# TinyShuffle_v_0b.net
KiCad netlist of a schematic drawn in Altium Designer
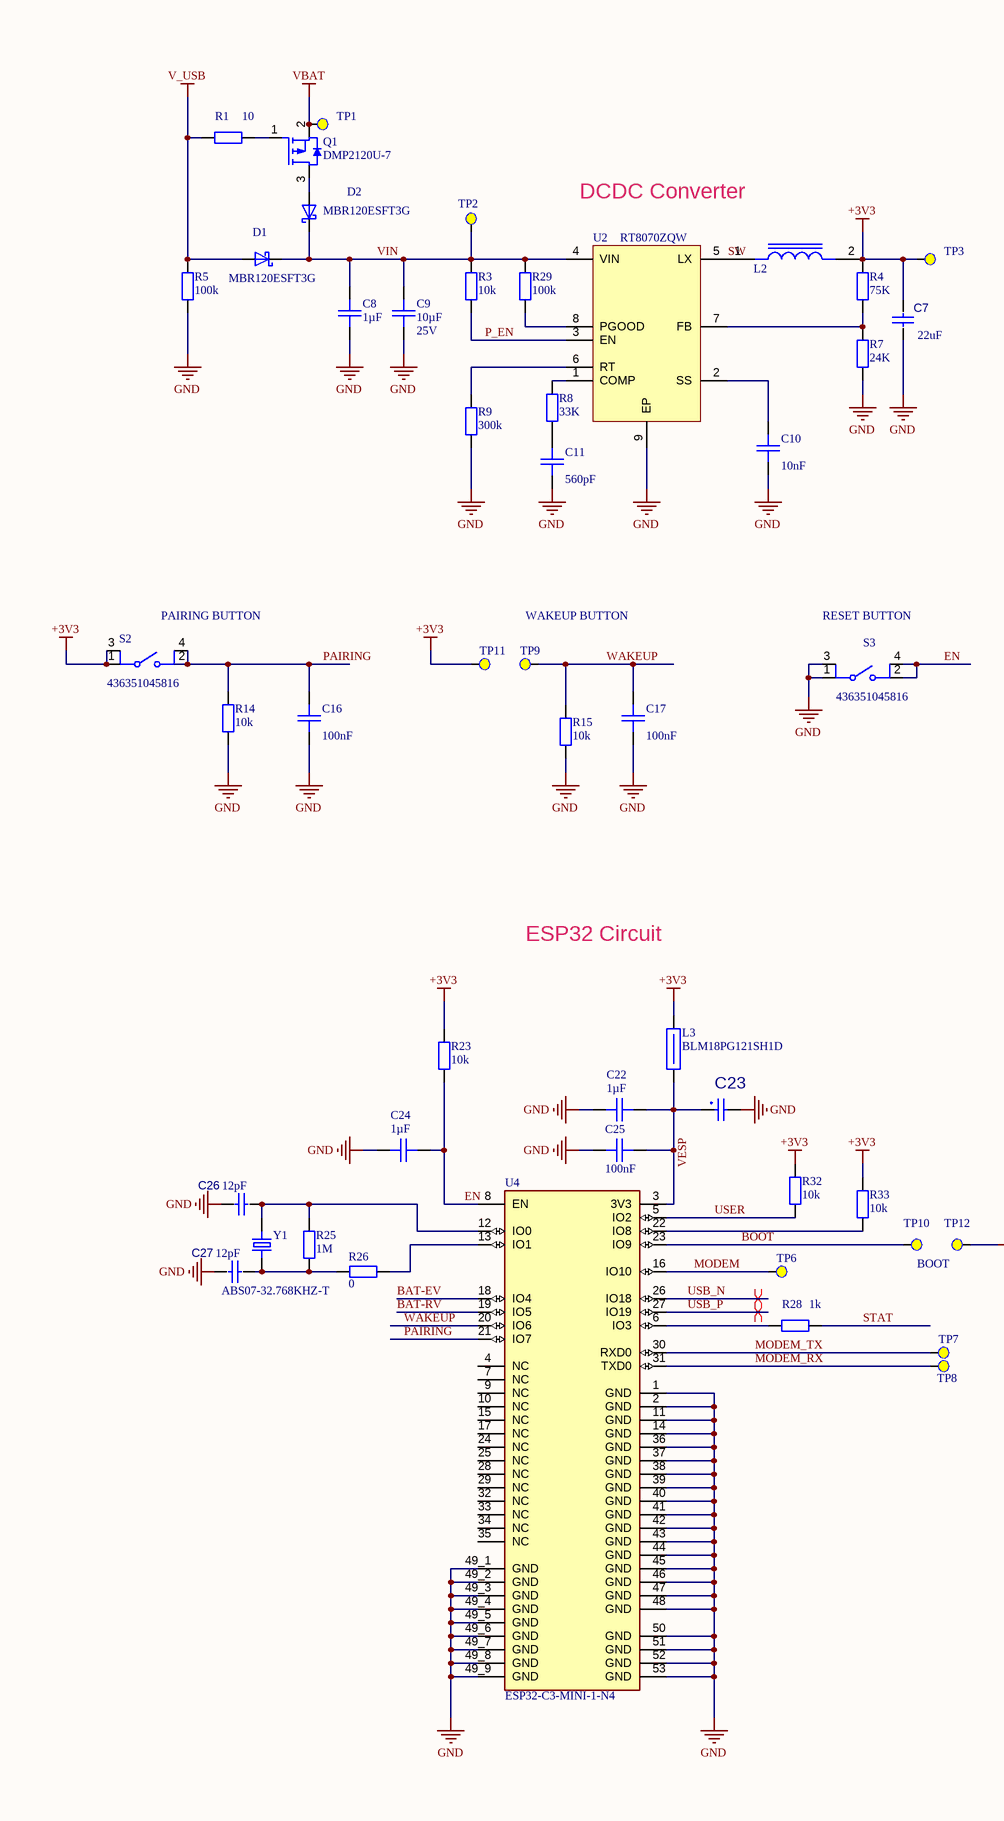
[diagram p0: TinyShuffle v.0b.SchDoc, left]
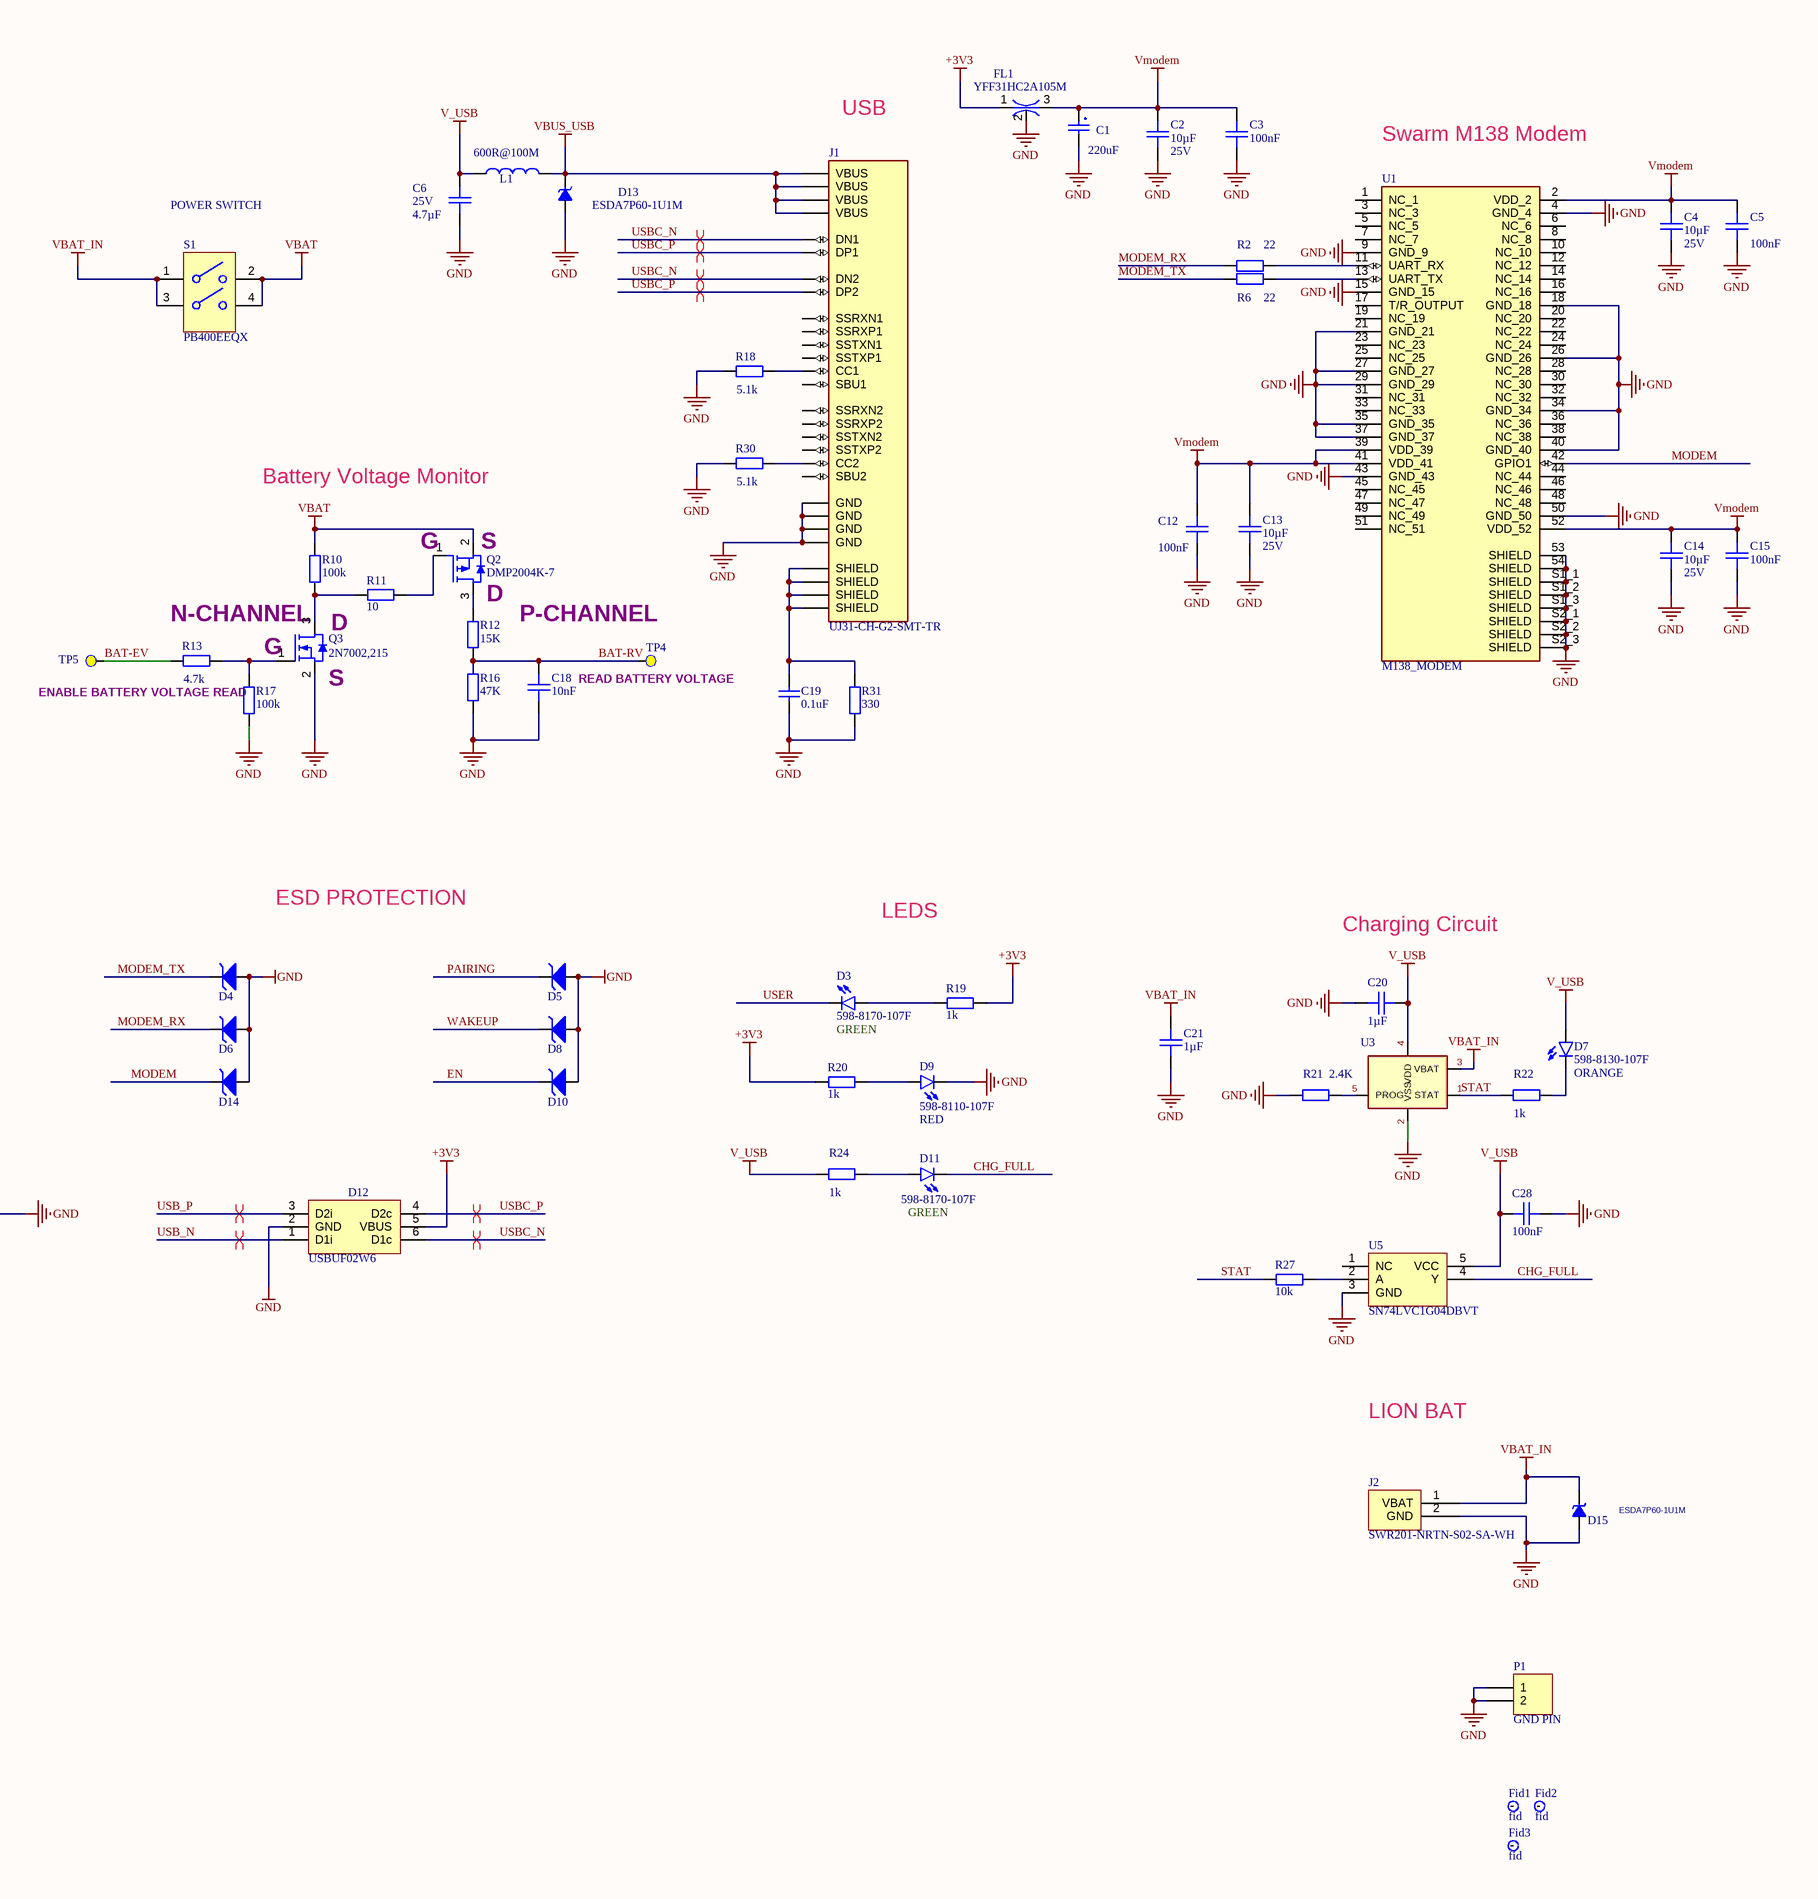
[diagram p1: TinyShuffle v.0b.SchDoc, right]

(export (version "E")
  (design (tool "Eeschema 10.0.6"))
  (components
    (comp (ref "C1")
      (value "APXA6R3ARA221MH7")
      (footprint "CHEMI-H70")
      (description "CAP ALUM POLY 220UF 20% 6.3V SMD")
      (fields
        (field (name "MANUFACTURER") "Nippon Chemi-Con")
        (field (name "MPN") "APXA6R3ARA221MH70G")
        (field (name "CAPACITANCE") "220uF")
      )
      (libsource (lib "TinyShuffle v.0b") (part "APXA6R3ARA221MH7"))
    )
    (comp (ref "C2")
      (value "GRM188R61E106MA73J")
      (footprint "CAPC160X80X90L35L")
      (description "CAP CER 10UF 25V X5R 0603")
      (fields
        (field (name "TOLERANCE") "20%")
        (field (name "MANUFACTURER") "Murata Electronics")
        (field (name "CAPACITANCE") "10µF")
        (field (name "VOLTAGE RATING") "25V")
      )
      (libsource (lib "VDroid Server") (part "CAP general symbol S00567"))
    )
    (comp (ref "C3")
      (value "CL10B104KB8NNWC")
      (footprint "CAPC160X80X90L35L")
      (description "CAP CER 0.1UF 50V X7R 0603")
      (fields
        (field (name "CAPACITANCE") "100nF")
        (field (name "TOLERANCE") "10%")
        (field (name "MANUFACTURER") "Samsung Electro-Mechanics")
      )
      (libsource (lib "VDroid Server") (part "CAP general symbol S00567"))
    )
    (comp (ref "C4")
      (value "GRM188R61E106MA73J")
      (footprint "CAPC160X80X90L35L")
      (description "CAP CER 10UF 25V X5R 0603")
      (fields
        (field (name "TOLERANCE") "20%")
        (field (name "MANUFACTURER") "Murata Electronics")
        (field (name "CAPACITANCE") "10µF")
        (field (name "VOLTAGE RATING") "25V")
      )
      (libsource (lib "VDroid Server") (part "CAP general symbol S00567"))
    )
    (comp (ref "C5")
      (value "CL10B104KB8NNWC")
      (footprint "CAPC160X80X90L35L")
      (description "CAP CER 0.1UF 50V X7R 0603")
      (fields
        (field (name "CAPACITANCE") "100nF")
        (field (name "TOLERANCE") "10%")
        (field (name "MANUFACTURER") "Samsung Electro-Mechanics")
      )
      (libsource (lib "VDroid Server") (part "CAP general symbol S00567"))
    )
    (comp (ref "C6")
      (value "GRM188R61E475KE11D")
      (footprint "CAPC160X80X90L35L")
      (description "CAP CER 4.7UF 25V X5R 0603")
      (fields
        (field (name "VOLTAGE RATING") "25V")
        (field (name "TOLERANCE") "10%")
        (field (name "CAPACITANCE") "4.7µF")
        (field (name "MANUFACTURER") "Murata Electronics")
      )
      (libsource (lib "VDroid Server") (part "CAP general symbol S00567"))
    )
    (comp (ref "C7")
      (value "22uF")
      (footprint "CAPC2012X135N")
      (description "CAP CER 22UF 16V X5R 0805")
      (fields
        (field (name "MANUFACTURER") "Samsung Electro-Mechanics")
        (field (name "MPN") "CL21A226MOQNNNE")
      )
      (libsource (lib "TinyShuffle v.0") (part "CL21A226MOQNNNE"))
    )
    (comp (ref "C8")
      (value "CL10A105KA8NNNC")
      (footprint "CAPC160X80X90L35L")
      (description "CAP CER 1UF 25V X5R 0603")
      (fields
        (field (name "MANUFACTURER") "Samsung Electro-Mechanics")
        (field (name "TOLERANCE") "10%")
        (field (name "CAPACITANCE") "1µF")
      )
      (libsource (lib "VDroid Server") (part "CAP general symbol S00567"))
    )
    (comp (ref "C9")
      (value "GRM188R61E106MA73J")
      (footprint "CAPC160X80X90L35L")
      (description "CAP CER 10UF 25V X5R 0603")
      (fields
        (field (name "TOLERANCE") "20%")
        (field (name "MANUFACTURER") "Murata Electronics")
        (field (name "CAPACITANCE") "10µF")
        (field (name "VOLTAGE RATING") "25V")
      )
      (libsource (lib "VDroid Server") (part "CAP general symbol S00567"))
    )
    (comp (ref "C10")
      (value "CL10B103KB8NNNC")
      (footprint "CAPC160X80X90L35L")
      (description "CAP CER 10000PF 50V X7R 0603")
      (fields
        (field (name "CAPACITANCE") "10nF")
        (field (name "TOLERANCE") "10%")
        (field (name "MANUFACTURER") "Samsung Electro-Mechanics")
      )
      (libsource (lib "VDroid Server") (part "CAP general symbol S00567"))
    )
    (comp (ref "C11")
      (value "CL10C561JB8NFNC")
      (footprint "CAPC160X80X90L35L")
      (description "CAP CER 560PF 50V C0G/NP0 0603")
      (fields
        (field (name "CAPACITANCE") "560pF")
        (field (name "TOLERANCE") "10%")
        (field (name "MANUFACTURER") "Samsung Electro-Mechanics")
      )
      (libsource (lib "VDroid Server") (part "CAP general symbol S00567"))
    )
    (comp (ref "C12")
      (value "CL10B104KB8NNWC")
      (footprint "CAPC160X80X90L35L")
      (description "CAP CER 0.1UF 50V X7R 0603")
      (fields
        (field (name "CAPACITANCE") "100nF")
        (field (name "TOLERANCE") "10%")
        (field (name "MANUFACTURER") "Samsung Electro-Mechanics")
      )
      (libsource (lib "VDroid Server") (part "CAP general symbol S00567"))
    )
    (comp (ref "C13")
      (value "GRM188R61E106MA73J")
      (footprint "CAPC160X80X90L35L")
      (description "CAP CER 10UF 25V X5R 0603")
      (fields
        (field (name "TOLERANCE") "20%")
        (field (name "MANUFACTURER") "Murata Electronics")
        (field (name "CAPACITANCE") "10µF")
        (field (name "VOLTAGE RATING") "25V")
      )
      (libsource (lib "VDroid Server") (part "CAP general symbol S00567"))
    )
    (comp (ref "C14")
      (value "GRM188R61E106MA73J")
      (footprint "CAPC160X80X90L35L")
      (description "CAP CER 10UF 25V X5R 0603")
      (fields
        (field (name "TOLERANCE") "20%")
        (field (name "MANUFACTURER") "Murata Electronics")
        (field (name "CAPACITANCE") "10µF")
        (field (name "VOLTAGE RATING") "25V")
      )
      (libsource (lib "VDroid Server") (part "CAP general symbol S00567"))
    )
    (comp (ref "C15")
      (value "CL10B104KB8NNWC")
      (footprint "CAPC160X80X90L35L")
      (description "CAP CER 0.1UF 50V X7R 0603")
      (fields
        (field (name "CAPACITANCE") "100nF")
        (field (name "TOLERANCE") "10%")
        (field (name "MANUFACTURER") "Samsung Electro-Mechanics")
      )
      (libsource (lib "VDroid Server") (part "CAP general symbol S00567"))
    )
    (comp (ref "C16")
      (value "CL10B104KB8NNWC")
      (footprint "CAPC160X80X90L35L")
      (description "CAP CER 0.1UF 50V X7R 0603")
      (fields
        (field (name "CAPACITANCE") "100nF")
        (field (name "TOLERANCE") "10%")
        (field (name "MANUFACTURER") "Samsung Electro-Mechanics")
      )
      (libsource (lib "VDroid Server") (part "CAP general symbol S00567"))
    )
    (comp (ref "C17")
      (value "CL10B104KB8NNWC")
      (footprint "CAPC160X80X90L35L")
      (description "CAP CER 0.1UF 50V X7R 0603")
      (fields
        (field (name "CAPACITANCE") "100nF")
        (field (name "TOLERANCE") "10%")
        (field (name "MANUFACTURER") "Samsung Electro-Mechanics")
      )
      (libsource (lib "VDroid Server") (part "CAP general symbol S00567"))
    )
    (comp (ref "C18")
      (value "GCM1885C1H103JA16D")
      (footprint "CAPC160X80X90L35L")
      (description "CAP CER 10000PF 50V NP0 0603")
      (fields
        (field (name "CAPACITANCE") "10nF")
        (field (name "TOLERANCE") "5%")
        (field (name "MANUFACTURER") "Murata Electronics")
      )
      (libsource (lib "VDroid Server") (part "CAP general symbol S00567"))
    )
    (comp (ref "C19")
      (value "0.1uF")
      (footprint "0603 CAP")
      (description "CAP CER 0.1UF 100V X7R 0603")
      (fields (field (name "MANUFACTURER") "Samsung") (field (name "MPN") "CL10B104KC8NNNC"))
      (libsource (lib "Capacitors") (part "0603-X7R-100V-0.1uF"))
    )
    (comp (ref "C20")
      (value "CL10A105KA8NNNC")
      (footprint "CAPC160X80X90L35L")
      (description "CAP CER 1UF 25V X5R 0603")
      (fields
        (field (name "MANUFACTURER") "Samsung Electro-Mechanics")
        (field (name "TOLERANCE") "10%")
        (field (name "CAPACITANCE") "1µF")
      )
      (libsource (lib "VDroid Server") (part "CAP general symbol S00567"))
    )
    (comp (ref "C21")
      (value "CL10A105KA8NNNC")
      (footprint "CAPC160X80X90L35L")
      (description "CAP CER 1UF 25V X5R 0603")
      (fields
        (field (name "MANUFACTURER") "Samsung Electro-Mechanics")
        (field (name "TOLERANCE") "10%")
        (field (name "CAPACITANCE") "1µF")
      )
      (libsource (lib "VDroid Server") (part "CAP general symbol S00567"))
    )
    (comp (ref "C22")
      (value "CL10A105KA8NNNC")
      (footprint "CAPC160X80X90L35L")
      (description "CAP CER 1UF 25V X5R 0603")
      (fields
        (field (name "MANUFACTURER") "Samsung Electro-Mechanics")
        (field (name "TOLERANCE") "10%")
        (field (name "CAPACITANCE") "1µF")
      )
      (libsource (lib "VDroid Server") (part "CAP general symbol S00567"))
    )
    (comp (ref "C23")
      (value "APXA6R3ARA221MH7")
      (footprint "CHEMI-H70")
      (description "CAP ALUM POLY 220UF 20% 6.3V SMD")
      (fields (field (name "MANUFACTURER") "Nippon Chemi-Con") (field (name "MPN") "APXA6R3ARA221MH70G"))
      (libsource (lib "TinyShuffle v.0b") (part "APXA6R3ARA221MH7"))
    )
    (comp (ref "C24")
      (value "CL10A105KA8NNNC")
      (footprint "CAPC160X80X90L35L")
      (description "CAP CER 1UF 25V X5R 0603")
      (fields
        (field (name "MANUFACTURER") "Samsung Electro-Mechanics")
        (field (name "TOLERANCE") "10%")
        (field (name "CAPACITANCE") "1µF")
      )
      (libsource (lib "VDroid Server") (part "CAP general symbol S00567"))
    )
    (comp (ref "C25")
      (value "CL10B104KB8NNWC")
      (footprint "CAPC160X80X90L35L")
      (description "CAP CER 0.1UF 50V X7R 0603")
      (fields
        (field (name "CAPACITANCE") "100nF")
        (field (name "TOLERANCE") "10%")
        (field (name "MANUFACTURER") "Samsung Electro-Mechanics")
      )
      (libsource (lib "VDroid Server") (part "CAP general symbol S00567"))
    )
    (comp (ref "C26")
      (value "12pF")
      (footprint "0603 Capacitor")
      (description "CAP CER 12PF NP0 0603")
      (fields (field (name "MANUFACTURER") "Murata Electronics") (field (name "MPN") "GRM1885C1H120JA01J"))
      (libsource (lib "*") (part "CAPC1608N-0.1UF"))
    )
    (comp (ref "C27")
      (value "12pF")
      (footprint "0603 Capacitor")
      (description "CAP CER 12PF NP0 0603")
      (fields (field (name "MANUFACTURER") "Murata Electronics") (field (name "MPN") "GRM1885C1H120JA01J"))
      (libsource (lib "*") (part "CAPC1608N-0.1UF"))
    )
    (comp (ref "C28")
      (value "CL10B104KB8NNWC")
      (footprint "CAPC160X80X90L35L")
      (description "CAP CER 0.1UF 50V X7R 0603")
      (fields
        (field (name "CAPACITANCE") "100nF")
        (field (name "TOLERANCE") "10%")
        (field (name "MANUFACTURER") "Samsung Electro-Mechanics")
      )
      (libsource (lib "VDroid Server") (part "CAP general symbol S00567"))
    )
    (comp (ref "D1")
      (value "MBR120ESFT3G")
      (footprint "SODFL3616X98N")
      (description "DIODE SCHOTTKY 20V 1A SOD123FL")
      (fields (field (name "GENERIC PART") "no") (field (name "MANUFACTURER") "ON"))
      (libsource (lib "TinyShuffle v.0b") (part "MBR0520"))
    )
    (comp (ref "D2")
      (value "MBR120ESFT3G")
      (footprint "SODFL3616X98N")
      (description "DIODE SCHOTTKY 20V 1A SOD123FL")
      (fields (field (name "GENERIC PART") "no") (field (name "MANUFACTURER") "ON"))
      (libsource (lib "TinyShuffle v.0b") (part "MBR0520"))
    )
    (comp (ref "D3")
      (value "598-8170-107F")
      (footprint "LEDC2012X70N")
      (description "Green 566nm LED Indication - Discrete 2V 0805 (2012 Metric)")
      (fields (field (name "MANUFACTURER") "Dialight") (field (name "ALTIUM_VALUE") "GREEN"))
      (libsource (lib "TinyShuffle v.0") (part "598_SERIES_LED"))
    )
    (comp (ref "D4")
      (value "CDSOD323-T03SC")
      (footprint "SOD2513X120N")
      (description "TVS DIODE 3.3VWM 10.9VC SOD323")
      (fields (field (name "MANUFACTURER") "Bourns Inc."))
      (libsource (lib "TinyShuffle v.0b") (part "CDSOD323-T03SC"))
    )
    (comp (ref "D5")
      (value "CDSOD323-T03SC")
      (footprint "SOD2513X120N")
      (description "TVS DIODE 3.3VWM 10.9VC SOD323")
      (fields (field (name "MANUFACTURER") "Bourns Inc."))
      (libsource (lib "TinyShuffle v.0b") (part "CDSOD323-T03SC"))
    )
    (comp (ref "D6")
      (value "CDSOD323-T03SC")
      (footprint "SOD2513X120N")
      (description "TVS DIODE 3.3VWM 10.9VC SOD323")
      (fields (field (name "MANUFACTURER") "Bourns Inc."))
      (libsource (lib "TinyShuffle v.0b") (part "CDSOD323-T03SC"))
    )
    (comp (ref "D7")
      (value "598-8130-107F")
      (footprint "TinyShuffle v.0:LEDC2012X70N")
      (description "Orange 605nm LED Indication - Discrete 2V 0805 (2012 Metric)")
      (fields (field (name "MANUFACTURER") "Dialight") (field (name "ALTIUM_VALUE") "ORANGE"))
      (libsource (lib "TinyShuffle v.0") (part "598_SERIES_LED"))
    )
    (comp (ref "D8")
      (value "CDSOD323-T03SC")
      (footprint "SOD2513X120N")
      (description "TVS DIODE 3.3VWM 10.9VC SOD323")
      (fields (field (name "MANUFACTURER") "Bourns Inc."))
      (libsource (lib "TinyShuffle v.0b") (part "CDSOD323-T03SC"))
    )
    (comp (ref "D9")
      (value "598-8110-107F")
      (footprint "TinyShuffle v.0:LEDC2012X70N")
      (description "Red 635nm LED Indication - Discrete 2.2V 0805 _2012 Metric_")
      (fields (field (name "MANUFACTURER") "Dialight") (field (name "ALTIUM_VALUE") "RED"))
      (libsource (lib "TinyShuffle v.0") (part "598_SERIES_LED"))
    )
    (comp (ref "D10")
      (value "CDSOD323-T03SC")
      (footprint "SOD2513X120N")
      (description "TVS DIODE 3.3VWM 10.9VC SOD323")
      (fields (field (name "MANUFACTURER") "Bourns Inc."))
      (libsource (lib "TinyShuffle v.0b") (part "CDSOD323-T03SC"))
    )
    (comp (ref "D11")
      (value "598-8170-107F")
      (footprint "TinyShuffle v.0:LEDC2012X70N")
      (description "Green 566nm LED Indication - Discrete 2V 0805 (2012 Metric)")
      (fields (field (name "MANUFACTURER") "Dialight") (field (name "ALTIUM_VALUE") "GREEN"))
      (libsource (lib "TinyShuffle v.0") (part "598_SERIES_LED"))
    )
    (comp (ref "D12")
      (value "USBUF02W6")
      (footprint "SOT323-6L")
      (description "FILTER RC(PI) 22 OHM/47PF SMD")
      (fields (field (name "MANUFACTURER") "STMicroelectronics"))
      (libsource (lib "Diodes") (part "NUF2221W1T2G"))
    )
    (comp (ref "D13")
      (value "ESDA7P60-1U1M")
      (footprint "ST_1610")
      (description "TVS DIODE 5V 11.6V 1610")
      (fields (field (name "MANUFACTURER") "STMicroelectronics"))
      (libsource (lib "Diodes") (part "ESDA7P60-1U1M"))
    )
    (comp (ref "D14")
      (value "CDSOD323-T03SC")
      (footprint "SOD2513X120N")
      (description "TVS DIODE 3.3VWM 10.9VC SOD323")
      (fields (field (name "MANUFACTURER") "Bourns Inc."))
      (libsource (lib "TinyShuffle v.0b") (part "CDSOD323-T03SC"))
    )
    (comp (ref "D15")
      (value "ESDA7P60-1U1M")
      (footprint "ST_1610")
      (description "TVS DIODE 5V 11.6V 1610")
      (fields (field (name "MANUFACTURER") "STMicroelectronics"))
      (libsource (lib "Diodes") (part "ESDA7P60-1U1M"))
    )
    (comp (ref "Fid1") (value "fid") (footprint "Fiducial mark 1") (libsource (lib "SensiEdge") (part "fid")))
    (comp (ref "Fid2") (value "fid") (footprint "Fiducial mark 1") (libsource (lib "SensiEdge") (part "fid")))
    (comp (ref "Fid3") (value "fid") (footprint "Fiducial mark 1") (libsource (lib "SensiEdge") (part "fid")))
    (comp (ref "FL1")
      (value "YFF31HC2A105M")
      (footprint "FIL_YFF31HC2A105M")
      (description "1ÂµF Feed Through Capacitor 100V 6A 5mOhm 1206 (3216 Metric), 4 PC Pad")
      (fields (field (name "MANUFACTURER") "TDK") (field (name "DIGI-KEY_PART_NUMBER") "445-16151-1-ND"))
      (libsource (lib "TinyShuffle v.0") (part "YFF31HC2A105M"))
    )
    (comp (ref "J1")
      (value "UJ31-CH-G2-SMT-TR")
      (footprint "CUI_UJ31-CH-G2-SMT-TR")
      (description "Type C, USB 3.1 Gen 2, 5 A, Right Angle, Surface Mount _SMT_, USB Receptacle")
      (fields (field (name "MANUFACTURER") "CUI Devices"))
      (libsource (lib "TinyShuffle v.0b") (part "UJ31-CH-G2-SMT-TR"))
    )
    (comp (ref "J2")
      (value "SWR201-NRTN-S02-SA-WH")
      (footprint "JST_B2B-PH-K-S(LF)(SN)")
      (description "Connector Header, PH Series, 2 Position, 2.00mm, Through Hole, Press-Fit, Solder, Natural")
      (fields (field (name "MANUFACTURER") "Sullins Connector Solutions"))
      (libsource (lib "Schlib1") (part "Battery Connector"))
    )
    (comp (ref "L1")
      (value "600R@100M")
      (footprint "0805 Ferrite Bead 2012")
      (description "FERRITE BEAD 600 OHM 0805 2A")
      (fields (field (name "MANUFACTURER") "Vishay Dale") (field (name "MPN") "ILHB0805ER601V"))
      (libsource (lib "Inductors") (part "ILHB0805ER601V"))
    )
    (comp (ref "L2")
      (value "SRP4020FA-2R0M")
      (footprint "IND_SRP4020FA-1R0M")
      (description "2 µH Shielded Drum Core, Wirewound Inductor 8.2 A 23.3mOhm Max Nonstandard -")
      (fields (field (name "MANUFACTURER") "Bourns Inc.") (field (name "TOLERANCE") "20%"))
      (libsource (lib "TinyShuffle v.0b") (part "SRP4020FA-2R0M"))
    )
    (comp (ref "L3")
      (value "BLM18PG121SH1D")
      (footprint "0603 Ferrite Bead 1608")
      (description "FERRITE BEAD 120 OHM 0603 1LN")
      (fields (field (name "MANUFACTURER") "Murata Electronics North America"))
      (libsource (lib "Acorai-WearablePatch") (part "ferrite bead"))
    )
    (comp (ref "P1")
      (value "GND PIN")
      (footprint "HDR1X2")
      (description "Header, 2-Pin")
      (fields (field (name "PUBLISHER") "Altium Limited"))
      (libsource (lib "Miscellaneous Connectors") (part "Header 2"))
    )
    (comp (ref "Q1")
      (value "DMP2120U-7")
      (footprint "SOT23-3P95_237X112L50X40L")
      (description "MOSFET P-CH 20V 3.8A SOT23")
      (fields (field (name "MANUFACTURER") "Diodes Incorporated"))
      (libsource (lib "VDroid Server") (part "P-type channel MOSFET S00673 (1-G 2-S 3-D)"))
    )
    (comp (ref "Q2")
      (value "DMP2004K-7")
      (footprint "SOT23-3P95_237X112L50X40L")
      (description "MOSFET P-CH 20V 600MA SOT23-3")
      (fields (field (name "MANUFACTURER") "Diodes Incorporated"))
      (libsource (lib "VDroid Server") (part "P-type channel MOSFET S00673 (1-G 2-S 3-D)"))
    )
    (comp (ref "Q3")
      (value "2N7002,215")
      (footprint "SOT23-3P95_237X112L50X40L")
      (description "Power MOSFET, N Channel, 60 V, 300 mA, 2.8 ohm, SOT-23, Surface Mount")
      (fields (field (name "MANUFACTURER") "Nexperia USA Inc."))
      (libsource (lib "VDroid Server") (part "N-type channel MOSFET S00674 (1-G 2-S 3-D)"))
    )
    (comp (ref "R1")
      (value "RC0603FR-0710RL")
      (footprint "RESC160X80X45L30L")
      (description "RES 10 OHM 1% 1/10W 0603")
      (fields (field (name "RESISTANCE") "10") (field (name "POWER") "100mW") (field (name "TOLERANCE") "1%"))
      (libsource (lib "VDroid Server") (part "RES general symbol S00555"))
    )
    (comp (ref "R2")
      (value "RC0603FR-0722RL")
      (footprint "RESC160X80X45L30L")
      (description "RES 22 OHM 1% 1/10W 0603")
      (fields (field (name "RESISTANCE") "22") (field (name "POWER") "100mW") (field (name "TOLERANCE") "1%"))
      (libsource (lib "VDroid Server") (part "RES general symbol S00555"))
    )
    (comp (ref "R3")
      (value "RT0603DRD0710KL")
      (footprint "RESC160X80X45L30L")
      (description "RES SMD 10K OHM 0.5% 1/10W 0603")
      (fields
        (field (name "MANUFACTURER") "YAGEO")
        (field (name "POWER") "100mW")
        (field (name "RESISTANCE") "10k")
      )
      (libsource (lib "VDroid Server") (part "RES general symbol S00555"))
    )
    (comp (ref "R4")
      (value "RC0603FR-0775KL")
      (footprint "RESC160X80X45L30L")
      (description "RES 75K OHM 1% 1/10W 0603")
      (fields
        (field (name "RESISTANCE") "75K")
        (field (name "POWER") "100mW")
        (field (name "TOLERANCE") "1%")
      )
      (libsource (lib "VDroid Server") (part "RES general symbol S00555"))
    )
    (comp (ref "R5")
      (value "RC0603FR-07100KL")
      (footprint "RESC160X80X45L30L")
      (description "RES 100K OHM 1% 1/10W 0603")
      (fields
        (field (name "RESISTANCE") "100k")
        (field (name "POWER") "100mW")
        (field (name "TOLERANCE") "1%")
      )
      (libsource (lib "VDroid Server") (part "RES general symbol S00555"))
    )
    (comp (ref "R6")
      (value "RC0603FR-0722RL")
      (footprint "RESC160X80X45L30L")
      (description "RES 22 OHM 1% 1/10W 0603")
      (fields (field (name "RESISTANCE") "22") (field (name "POWER") "100mW") (field (name "TOLERANCE") "1%"))
      (libsource (lib "VDroid Server") (part "RES general symbol S00555"))
    )
    (comp (ref "R7")
      (value "RC0603FR-0724KL")
      (footprint "RESC160X80X45L30L")
      (description "RES 24K OHM 1% 1/10W 0603")
      (fields
        (field (name "RESISTANCE") "24K")
        (field (name "POWER") "100mW")
        (field (name "TOLERANCE") "1%")
      )
      (libsource (lib "VDroid Server") (part "RES general symbol S00555"))
    )
    (comp (ref "R8")
      (value "RC0603FR-0733KL")
      (footprint "RESC160X80X45L30L")
      (description "RES 33K OHM 1% 1/10W 0603")
      (fields
        (field (name "RESISTANCE") "33K")
        (field (name "POWER") "100mW")
        (field (name "TOLERANCE") "1%")
      )
      (libsource (lib "VDroid Server") (part "RES general symbol S00555"))
    )
    (comp (ref "R9")
      (value "RC0603FR-07300KL")
      (footprint "RESC160X80X45L30L")
      (description "RES 300K OHM 1% 1/10W 0603")
      (fields
        (field (name "RESISTANCE") "300k")
        (field (name "POWER") "100mW")
        (field (name "TOLERANCE") "1%")
      )
      (libsource (lib "VDroid Server") (part "RES general symbol S00555"))
    )
    (comp (ref "R10")
      (value "RC0603FR-07100KL")
      (footprint "RESC160X80X45L30L")
      (description "RES 100K OHM 1% 1/10W 0603")
      (fields
        (field (name "RESISTANCE") "100k")
        (field (name "POWER") "100mW")
        (field (name "TOLERANCE") "1%")
      )
      (libsource (lib "VDroid Server") (part "RES general symbol S00555"))
    )
    (comp (ref "R11")
      (value "RC0603FR-0710RL")
      (footprint "RESC160X80X45L30L")
      (description "RES 10 OHM 1% 1/10W 0603")
      (fields (field (name "RESISTANCE") "10") (field (name "POWER") "100mW") (field (name "TOLERANCE") "1%"))
      (libsource (lib "VDroid Server") (part "RES general symbol S00555"))
    )
    (comp (ref "R12")
      (value "RC0603FR-0715KL")
      (footprint "RESC160X80X45L30L")
      (description "RES 15K OHM 1% 1/10W 0603")
      (fields
        (field (name "RESISTANCE") "15K")
        (field (name "POWER") "100mW")
        (field (name "TOLERANCE") "1%")
      )
      (libsource (lib "VDroid Server") (part "RES general symbol S00555"))
    )
    (comp (ref "R13")
      (value "RC0603FR-074K7P")
      (footprint "RESC160X80X45L30L")
      (description "RES SMD 4.7K OHM 1% 1/10W 0603")
      (fields
        (field (name "RESISTANCE") "4.7k")
        (field (name "TOLERANCE") "1%")
        (field (name "MANUFACTURER") "YAGEO")
      )
      (libsource (lib "VDroid Server") (part "RES general symbol S00555"))
    )
    (comp (ref "R14")
      (value "RT0603DRD0710KL")
      (footprint "RESC160X80X45L30L")
      (description "RES SMD 10K OHM 0.5% 1/10W 0603")
      (fields
        (field (name "MANUFACTURER") "YAGEO")
        (field (name "POWER") "100mW")
        (field (name "RESISTANCE") "10k")
      )
      (libsource (lib "VDroid Server") (part "RES general symbol S00555"))
    )
    (comp (ref "R15")
      (value "RT0603DRD0710KL")
      (footprint "RESC160X80X45L30L")
      (description "RES SMD 10K OHM 0.5% 1/10W 0603")
      (fields
        (field (name "MANUFACTURER") "YAGEO")
        (field (name "POWER") "100mW")
        (field (name "RESISTANCE") "10k")
      )
      (libsource (lib "VDroid Server") (part "RES general symbol S00555"))
    )
    (comp (ref "R16")
      (value "RC0603FR-0747KL")
      (footprint "RESC160X80X45L30L")
      (description "RES 47K OHM 1% 1/10W 0603")
      (fields
        (field (name "RESISTANCE") "47K")
        (field (name "POWER") "100mW")
        (field (name "TOLERANCE") "1%")
      )
      (libsource (lib "VDroid Server") (part "RES general symbol S00555"))
    )
    (comp (ref "R17")
      (value "RC0603FR-07100KL")
      (footprint "RESC160X80X45L30L")
      (description "RES 100K OHM 1% 1/10W 0603")
      (fields
        (field (name "RESISTANCE") "100k")
        (field (name "POWER") "100mW")
        (field (name "TOLERANCE") "1%")
      )
      (libsource (lib "VDroid Server") (part "RES general symbol S00555"))
    )
    (comp (ref "R18")
      (value "RC0603FR-075K1L")
      (footprint "RESC160X80X45L30L")
      (description "RES 5.1K OHM 1% 1/10W 0603")
      (fields
        (field (name "RESISTANCE") "5.1k")
        (field (name "TOLERANCE") "1%")
        (field (name "MANUFACTURER") "YAGEO")
      )
      (libsource (lib "VDroid Server") (part "RES general symbol S00555"))
    )
    (comp (ref "R19")
      (value "RC0603FR-071KP")
      (footprint "RESC160X80X45L30L")
      (description "RES SMD 1K OHM 1% 1/10W 0603")
      (fields (field (name "RESISTANCE") "1k") (field (name "POWER") "100mW") (field (name "TOLERANCE") "1%"))
      (libsource (lib "VDroid Server") (part "RES general symbol S00555"))
    )
    (comp (ref "R20")
      (value "RC0603FR-071KP")
      (footprint "RESC160X80X45L30L")
      (description "RES SMD 1K OHM 1% 1/10W 0603")
      (fields (field (name "RESISTANCE") "1k") (field (name "POWER") "100mW") (field (name "TOLERANCE") "1%"))
      (libsource (lib "VDroid Server") (part "RES general symbol S00555"))
    )
    (comp (ref "R21")
      (value "RC0603FR-072K4L")
      (footprint "RESC160X80X45L30L")
      (description "RES 2.4K OHM 1% 1/10W 0603")
      (fields
        (field (name "RESISTANCE") "2.4K")
        (field (name "POWER") "100mW")
        (field (name "TOLERANCE") "1%")
      )
      (libsource (lib "VDroid Server") (part "RES general symbol S00555"))
    )
    (comp (ref "R22")
      (value "RC0603FR-071KP")
      (footprint "RESC160X80X45L30L")
      (description "RES SMD 1K OHM 1% 1/10W 0603")
      (fields (field (name "RESISTANCE") "1k") (field (name "POWER") "100mW") (field (name "TOLERANCE") "1%"))
      (libsource (lib "VDroid Server") (part "RES general symbol S00555"))
    )
    (comp (ref "R23")
      (value "RT0603DRD0710KL")
      (footprint "RESC160X80X45L30L")
      (description "RES SMD 10K OHM 0.5% 1/10W 0603")
      (fields
        (field (name "MANUFACTURER") "YAGEO")
        (field (name "POWER") "100mW")
        (field (name "RESISTANCE") "10k")
      )
      (libsource (lib "VDroid Server") (part "RES general symbol S00555"))
    )
    (comp (ref "R24")
      (value "RC0603FR-071KP")
      (footprint "RESC160X80X45L30L")
      (description "RES SMD 1K OHM 1% 1/10W 0603")
      (fields (field (name "RESISTANCE") "1k") (field (name "POWER") "100mW") (field (name "TOLERANCE") "1%"))
      (libsource (lib "VDroid Server") (part "RES general symbol S00555"))
    )
    (comp (ref "R25")
      (value "AC0603FR-071ML")
      (footprint "RESC160X80X45L30L")
      (description "RES SMD 1M OHM 1% 1/10W 0603")
      (fields
        (field (name "TOLERANCE") "1%")
        (field (name "MANUFACTURER") "YAGEO")
        (field (name "RESISTANCE") "1M")
      )
      (libsource (lib "VDroid Server") (part "RES general symbol S00555"))
    )
    (comp (ref "R26")
      (value "CRCW06030000Z0EA")
      (footprint "RESC160X80X45L30L")
      (description "RES SMD 0 OHM JUMPER 1/10W 0603")
      (fields
        (field (name "MANUFACTURER") "Vishay Dale")
        (field (name "TOLERANCE") "0%")
        (field (name "RESISTANCE") "0")
      )
      (libsource (lib "VDroid Server") (part "RES general symbol S00555"))
    )
    (comp (ref "R27")
      (value "RT0603DRD0710KL")
      (footprint "RESC160X80X45L30L")
      (description "RES SMD 10K OHM 0.5% 1/10W 0603")
      (fields
        (field (name "MANUFACTURER") "YAGEO")
        (field (name "POWER") "100mW")
        (field (name "RESISTANCE") "10k")
      )
      (libsource (lib "VDroid Server") (part "RES general symbol S00555"))
    )
    (comp (ref "R28")
      (value "RC0603FR-071KP")
      (footprint "RESC160X80X45L30L")
      (description "RES SMD 1K OHM 1% 1/10W 0603")
      (fields (field (name "RESISTANCE") "1k") (field (name "POWER") "100mW") (field (name "TOLERANCE") "1%"))
      (libsource (lib "VDroid Server") (part "RES general symbol S00555"))
    )
    (comp (ref "R29")
      (value "RC0603FR-07100KL")
      (footprint "RESC160X80X45L30L")
      (description "RES 100K OHM 1% 1/10W 0603")
      (fields
        (field (name "RESISTANCE") "100k")
        (field (name "POWER") "100mW")
        (field (name "TOLERANCE") "1%")
      )
      (libsource (lib "VDroid Server") (part "RES general symbol S00555"))
    )
    (comp (ref "R30")
      (value "RC0603FR-075K1L")
      (footprint "RESC160X80X45L30L")
      (description "RES 5.1K OHM 1% 1/10W 0603")
      (fields
        (field (name "RESISTANCE") "5.1k")
        (field (name "TOLERANCE") "1%")
        (field (name "MANUFACTURER") "YAGEO")
      )
      (libsource (lib "VDroid Server") (part "RES general symbol S00555"))
    )
    (comp (ref "R31")
      (value "RC0603FR-07330RL")
      (footprint "RESC160X80X45L30L")
      (description "RES 330 OHM 1% 1/10W 0603")
      (fields
        (field (name "RESISTANCE") "330")
        (field (name "TOLERANCE") "1%")
        (field (name "MANUFACTURER") "YAGEO")
      )
      (libsource (lib "VDroid Server") (part "RES general symbol S00555"))
    )
    (comp (ref "R32")
      (value "RT0603DRD0710KL")
      (footprint "RESC160X80X45L30L")
      (description "RES SMD 10K OHM 0.5% 1/10W 0603")
      (fields
        (field (name "MANUFACTURER") "YAGEO")
        (field (name "POWER") "100mW")
        (field (name "RESISTANCE") "10k")
      )
      (libsource (lib "VDroid Server") (part "RES general symbol S00555"))
    )
    (comp (ref "R33")
      (value "RT0603DRD0710KL")
      (footprint "RESC160X80X45L30L")
      (description "RES SMD 10K OHM 0.5% 1/10W 0603")
      (fields
        (field (name "MANUFACTURER") "YAGEO")
        (field (name "POWER") "100mW")
        (field (name "RESISTANCE") "10k")
      )
      (libsource (lib "VDroid Server") (part "RES general symbol S00555"))
    )
    (comp (ref "S1")
      (value "PB400EEQX")
      (footprint "SW_PB400EEQX")
      (description "Pushbutton Switch DPST Standard Through Hole, Right Angle")
      (fields (field (name "MANUFACTURER") "E-Switch"))
      (libsource (lib "TinyShuffle v.0b") (part "PB400EEQX"))
    )
    (comp (ref "S2")
      (value "436351045816")
      (footprint "436351045816")
      (description "Tactile Switch SPST-NO Side Actuated Surface Mount, Right Angle")
      (fields (field (name "MANUFACTURER") "Wurth Elektronik"))
      (libsource (lib "TinyShuffle v.0b") (part "436351045816"))
    )
    (comp (ref "S3")
      (value "436351045816")
      (footprint "436351045816")
      (description "Tactile Switch SPST-NO Side Actuated Surface Mount, Right Angle")
      (fields (field (name "MANUFACTURER") "Wurth Elektronik"))
      (libsource (lib "TinyShuffle v.0b") (part "436351045816"))
    )
    (comp (ref "TP1")
      (value "TPAD")
      (footprint "PAD_2.0R")
      (description "Test Pad, SMD")
      (libsource (lib "Others") (part "TPAD"))
    )
    (comp (ref "TP2")
      (value "TPAD")
      (footprint "PAD_2.0R")
      (description "Test Pad, SMD")
      (libsource (lib "Others") (part "TPAD"))
    )
    (comp (ref "TP3")
      (value "TPAD")
      (footprint "PAD_2.0R")
      (description "Test Pad, SMD")
      (libsource (lib "Others") (part "TPAD"))
    )
    (comp (ref "TP4")
      (value "TPAD")
      (footprint "PAD_2.0R")
      (description "Test Pad, SMD")
      (libsource (lib "Others") (part "TPAD"))
    )
    (comp (ref "TP5")
      (value "TPAD")
      (footprint "PAD_2.0R")
      (description "Test Pad, SMD")
      (libsource (lib "Others") (part "TPAD"))
    )
    (comp (ref "TP6")
      (value "TPAD")
      (footprint "PAD_2.0R")
      (description "Test Pad, SMD")
      (libsource (lib "Others") (part "TPAD"))
    )
    (comp (ref "TP7")
      (value "TPAD")
      (footprint "PAD_2.0R")
      (description "Test Pad, SMD")
      (libsource (lib "Others") (part "TPAD"))
    )
    (comp (ref "TP8")
      (value "TPAD")
      (footprint "PAD_2.0R")
      (description "Test Pad, SMD")
      (libsource (lib "Others") (part "TPAD"))
    )
    (comp (ref "TP9")
      (value "TPAD")
      (footprint "PAD_2.0R")
      (description "Test Pad, SMD")
      (libsource (lib "Others") (part "TPAD"))
    )
    (comp (ref "TP10")
      (value "TPAD")
      (footprint "PAD_2.0R")
      (description "Test Pad, SMD")
      (libsource (lib "Others") (part "TPAD"))
    )
    (comp (ref "TP11")
      (value "TPAD")
      (footprint "PAD_2.0R")
      (description "Test Pad, SMD")
      (libsource (lib "Others") (part "TPAD"))
    )
    (comp (ref "TP12")
      (value "TPAD")
      (footprint "PAD_2.0R")
      (description "Test Pad, SMD")
      (libsource (lib "Others") (part "TPAD"))
    )
    (comp (ref "U1")
      (value "M138_MODEM")
      (footprint "XCVR_M138_MODEM")
      (description "'SWARM M138 MODEM mPCIe 2.005\" (50.925mm) x 1.18\" (30mm)  Two part connector")
      (fields
        (field (name "MANUFACTURER") "Swarm")
        (field (name "MPN") "A: MM60-52B1-B1-R850 B: MM60-EZH039-B5-R850")
      )
      (libsource (lib "TinyShuffle v.0") (part "M138_MODEM"))
    )
    (comp (ref "U2")
      (value "RT8070ZQW")
      (footprint "QFN65P300X300X80_HS-9L")
      (description "IC REG BUCK ADJUSTABLE 4A 8WDFN")
      (fields (field (name "MANUFACTURER") "Richtek USA Inc."))
      (libsource (lib "TinyShuffle v.0") (part "RT8070ZQW"))
    )
    (comp (ref "U3")
      (value "MCP73831T-2ACI/OT")
      (footprint "SOT95P270X145-5N")
      (description "IC BATT CNTL LI-ION 1CEL SOT23-5")
      (fields (field (name "GENERIC PART") "no") (field (name "MANUFACTURER") "Microchip Technology"))
      (libsource (lib "TinyShuffle v.0b") (part "MCP73831-2-OT"))
    )
    (comp (ref "U4")
      (value "ESP32-C3-MINI-1-N4")
      (footprint "TinyShuffle v.0:XCVR_ESP32-C3-MINI-1-N4")
      (fields (field (name "MANUFACTURER") "Espressif Systems"))
      (libsource (lib "TinyShuffle v.0") (part "ESP32-C3-MINI-1-N4"))
    )
    (comp (ref "U5")
      (value "SN74LVC1G04DBVT")
      (footprint "SOT95P270X145-5N")
      (description "Inverter IC 1 Channel - SOT-23-5")
      (fields
        (field (name "MANUFACTURER") "Texas Instruments")
        (field (name "ARROW PART NUMBER") "SN74LVC1G04DBVR")
      )
      (libsource (lib "TinyShuffle v.0b") (part "SN74LVC1G04DBVR"))
    )
    (comp (ref "Y1")
      (value "ABS07-32.768KHZ-T")
      (footprint "TinyShuffle v.0:XTAL_ABS07-32.768KHZ-T")
      (description "32.768kHz Â±20ppm Crystal 12.5pF 70 kOhms 2-SMD, No Lead")
      (fields (field (name "MANUFACTURER") "Abracon LLC") (field (name "MPN") "ABS07-32.768KHZ"))
      (libsource (lib "TinyShuffle v.0") (part "ABS07-32.768KHZ-T"))
    )
  )
  (nets
    (net (code "1") (name "+3V3") (class "Default")
      (node (ref "C7") (pin "2") (pinfunction "2_2") (pintype "passive"))
      (node (ref "D12") (pin "5") (pinfunction "VBUS_5") (pintype "passive"))
      (node (ref "FL1") (pin "1") (pinfunction "IN/OUT_1") (pintype "passive"))
      (node (ref "L2") (pin "2") (pinfunction "2_2") (pintype "passive"))
      (node (ref "L3") (pin "2") (pintype "passive"))
      (node (ref "R19") (pin "1") (pinfunction "1_1") (pintype "passive"))
      (node (ref "R20") (pin "1") (pinfunction "1_1") (pintype "passive"))
      (node (ref "R23") (pin "2") (pinfunction "2_2") (pintype "passive"))
      (node (ref "R32") (pin "2") (pinfunction "2_2") (pintype "passive"))
      (node (ref "R33") (pin "2") (pinfunction "2_2") (pintype "passive"))
      (node (ref "R4") (pin "1") (pinfunction "1_1") (pintype "passive"))
      (node (ref "S2") (pin "1") (pinfunction "3_1") (pintype "passive"))
      (node (ref "S2") (pin "3") (pinfunction "1_3") (pintype "passive"))
      (node (ref "TP11") (pin "1") (pinfunction "TPoint_1") (pintype "passive"))
      (node (ref "TP3") (pin "1") (pinfunction "TPoint_1") (pintype "passive"))
    )
    (net (code "2") (name "/BAT-EV") (class "Default")
      (node (ref "R13") (pin "1") (pinfunction "1_1") (pintype "passive"))
      (node (ref "TP5") (pin "1") (pinfunction "TPoint_1") (pintype "passive"))
      (node (ref "U4") (pin "18") (pinfunction "IO4_18") (pintype "bidirectional"))
    )
    (net (code "3") (name "/BAT-RV") (class "Default")
      (node (ref "C18") (pin "2") (pinfunction "2_2") (pintype "passive"))
      (node (ref "R12") (pin "1") (pinfunction "1_1") (pintype "passive"))
      (node (ref "R16") (pin "1") (pinfunction "1_1") (pintype "passive"))
      (node (ref "TP4") (pin "1") (pinfunction "TPoint_1") (pintype "passive"))
      (node (ref "U4") (pin "19") (pinfunction "IO5_19") (pintype "bidirectional"))
    )
    (net (code "4") (name "/BOOT") (class "Default")
      (node (ref "TP10") (pin "1") (pinfunction "TPoint_1") (pintype "passive"))
      (node (ref "U4") (pin "23") (pinfunction "IO9_23") (pintype "bidirectional"))
    )
    (net (code "5") (name "/CHG_FULL") (class "Default")
      (node (ref "D11") (pin "C") (pinfunction "C_C") (pintype "passive"))
      (node (ref "U5") (pin "4") (pinfunction "Y_4") (pintype "passive"))
    )
    (net (code "6") (name "/EN") (class "Default")
      (node (ref "C24") (pin "1") (pinfunction "1_1") (pintype "passive"))
      (node (ref "D10") (pin "K") (pinfunction "K_K") (pintype "passive"))
      (node (ref "R23") (pin "1") (pinfunction "1_1") (pintype "passive"))
      (node (ref "S3") (pin "2") (pinfunction "4_2") (pintype "passive"))
      (node (ref "S3") (pin "4") (pinfunction "2_4") (pintype "passive"))
      (node (ref "U4") (pin "8") (pinfunction "EN_8") (pintype "passive"))
    )
    (net (code "7") (name "/MODEM") (class "Default")
      (node (ref "D14") (pin "K") (pinfunction "K_K") (pintype "passive"))
      (node (ref "TP6") (pin "1") (pinfunction "TPoint_1") (pintype "passive"))
      (node (ref "U1") (pin "42") (pinfunction "GPIO1_42") (pintype "bidirectional"))
      (node (ref "U4") (pin "16") (pinfunction "IO10_16") (pintype "bidirectional"))
    )
    (net (code "8") (name "/MODEM_RX") (class "Default")
      (node (ref "D6") (pin "K") (pinfunction "K_K") (pintype "passive"))
      (node (ref "R2") (pin "1") (pinfunction "1_1") (pintype "passive"))
      (node (ref "TP8") (pin "1") (pinfunction "TPoint_1") (pintype "passive"))
      (node (ref "U4") (pin "31") (pinfunction "TXD0_31") (pintype "bidirectional"))
    )
    (net (code "9") (name "/MODEM_TX") (class "Default")
      (node (ref "D4") (pin "K") (pinfunction "K_K") (pintype "passive"))
      (node (ref "R6") (pin "1") (pinfunction "1_1") (pintype "passive"))
      (node (ref "TP7") (pin "1") (pinfunction "TPoint_1") (pintype "passive"))
      (node (ref "U4") (pin "30") (pinfunction "RXD0_30") (pintype "bidirectional"))
    )
    (net (code "10") (name "/PAIRING") (class "Default")
      (node (ref "C16") (pin "2") (pinfunction "2_2") (pintype "passive"))
      (node (ref "D5") (pin "K") (pinfunction "K_K") (pintype "passive"))
      (node (ref "R14") (pin "2") (pinfunction "2_2") (pintype "passive"))
      (node (ref "S2") (pin "2") (pinfunction "4_2") (pintype "passive"))
      (node (ref "S2") (pin "4") (pinfunction "2_4") (pintype "passive"))
      (node (ref "U4") (pin "21") (pinfunction "IO7_21") (pintype "bidirectional"))
    )
    (net (code "11") (name "/P_EN") (class "Default")
      (node (ref "R3") (pin "1") (pinfunction "1_1") (pintype "passive"))
      (node (ref "U2") (pin "3") (pinfunction "EN_3") (pintype "passive"))
    )
    (net (code "12") (name "/STAT") (class "Default")
      (node (ref "R22") (pin "1") (pinfunction "1_1") (pintype "passive"))
      (node (ref "R27") (pin "1") (pinfunction "1_1") (pintype "passive"))
      (node (ref "R28") (pin "2") (pinfunction "2_2") (pintype "passive"))
      (node (ref "U3") (pin "1") (pinfunction "STAT_1") (pintype "passive"))
    )
    (net (code "13") (name "/SW") (class "Default")
      (node (ref "L2") (pin "1") (pinfunction "1_1") (pintype "passive"))
      (node (ref "U2") (pin "5") (pinfunction "LX_5") (pintype "passive"))
    )
    (net (code "14") (name "/USBC_N") (class "Default")
      (node (ref "D12") (pin "6") (pinfunction "D1c_6") (pintype "passive"))
      (node (ref "J1") (pin "A7") (pinfunction "DN1_A7") (pintype "bidirectional"))
      (node (ref "J1") (pin "B7") (pinfunction "DN2_B7") (pintype "bidirectional"))
    )
    (net (code "15") (name "/USBC_P") (class "Default")
      (node (ref "D12") (pin "4") (pinfunction "D2c_4") (pintype "passive"))
      (node (ref "J1") (pin "A6") (pinfunction "DP1_A6") (pintype "bidirectional"))
      (node (ref "J1") (pin "B6") (pinfunction "DP2_B6") (pintype "bidirectional"))
    )
    (net (code "16") (name "/USB_N") (class "Default")
      (node (ref "D12") (pin "1") (pinfunction "D1i_1") (pintype "passive"))
      (node (ref "U4") (pin "26") (pinfunction "IO18_26") (pintype "bidirectional"))
    )
    (net (code "17") (name "/USB_P") (class "Default")
      (node (ref "D12") (pin "3") (pinfunction "D2i_3") (pintype "passive"))
      (node (ref "U4") (pin "27") (pinfunction "IO19_27") (pintype "bidirectional"))
    )
    (net (code "18") (name "/USER") (class "Default")
      (node (ref "D3") (pin "C") (pinfunction "C_C") (pintype "passive"))
      (node (ref "R32") (pin "1") (pinfunction "1_1") (pintype "passive"))
      (node (ref "U4") (pin "5") (pinfunction "IO2_5") (pintype "bidirectional"))
    )
    (net (code "19") (name "/VESP") (class "Default")
      (node (ref "C22") (pin "1") (pinfunction "1_1") (pintype "passive"))
      (node (ref "C23") (pin "1") (pinfunction "1_1") (pintype "passive"))
      (node (ref "C25") (pin "1") (pinfunction "1_1") (pintype "passive"))
      (node (ref "L3") (pin "1") (pintype "passive"))
      (node (ref "U4") (pin "3") (pinfunction "3V3_3") (pintype "power_in"))
    )
    (net (code "20") (name "/VIN") (class "Default")
      (node (ref "C8") (pin "1") (pinfunction "1_1") (pintype "passive"))
      (node (ref "C9") (pin "2") (pinfunction "2_2") (pintype "passive"))
      (node (ref "D1") (pin "2") (pinfunction "K_2") (pintype "passive"))
      (node (ref "D2") (pin "2") (pinfunction "K_2") (pintype "passive"))
      (node (ref "R29") (pin "2") (pinfunction "2_2") (pintype "passive"))
      (node (ref "R3") (pin "2") (pinfunction "2_2") (pintype "passive"))
      (node (ref "TP2") (pin "1") (pinfunction "TPoint_1") (pintype "passive"))
      (node (ref "U2") (pin "4") (pinfunction "VIN_4") (pintype "passive"))
    )
    (net (code "21") (name "/WAKEUP") (class "Default")
      (node (ref "C17") (pin "2") (pinfunction "2_2") (pintype "passive"))
      (node (ref "D8") (pin "K") (pinfunction "K_K") (pintype "passive"))
      (node (ref "R15") (pin "2") (pinfunction "2_2") (pintype "passive"))
      (node (ref "TP9") (pin "1") (pinfunction "TPoint_1") (pintype "passive"))
      (node (ref "U4") (pin "20") (pinfunction "IO6_20") (pintype "bidirectional"))
    )
    (net (code "22") (name "GND") (class "Default")
      (node (ref "C1") (pin "2") (pinfunction "2_2") (pintype "passive"))
      (node (ref "C10") (pin "1") (pinfunction "1_1") (pintype "passive"))
      (node (ref "C11") (pin "1") (pinfunction "1_1") (pintype "passive"))
      (node (ref "C12") (pin "2") (pinfunction "2_2") (pintype "passive"))
      (node (ref "C13") (pin "1") (pinfunction "1_1") (pintype "passive"))
      (node (ref "C14") (pin "1") (pinfunction "1_1") (pintype "passive"))
      (node (ref "C15") (pin "1") (pinfunction "1_1") (pintype "passive"))
      (node (ref "C16") (pin "1") (pinfunction "1_1") (pintype "passive"))
      (node (ref "C17") (pin "1") (pinfunction "1_1") (pintype "passive"))
      (node (ref "C18") (pin "1") (pinfunction "1_1") (pintype "passive"))
      (node (ref "C19") (pin "2") (pintype "passive"))
      (node (ref "C2") (pin "1") (pinfunction "1_1") (pintype "passive"))
      (node (ref "C20") (pin "2") (pinfunction "2_2") (pintype "passive"))
      (node (ref "C21") (pin "2") (pinfunction "2_2") (pintype "passive"))
      (node (ref "C22") (pin "2") (pinfunction "2_2") (pintype "passive"))
      (node (ref "C23") (pin "2") (pinfunction "2_2") (pintype "passive"))
      (node (ref "C24") (pin "2") (pinfunction "2_2") (pintype "passive"))
      (node (ref "C25") (pin "2") (pinfunction "2_2") (pintype "passive"))
      (node (ref "C26") (pin "2") (pinfunction "2_2") (pintype "passive"))
      (node (ref "C27") (pin "2") (pinfunction "2_2") (pintype "passive"))
      (node (ref "C28") (pin "1") (pinfunction "1_1") (pintype "passive"))
      (node (ref "C3") (pin "1") (pinfunction "1_1") (pintype "passive"))
      (node (ref "C4") (pin "1") (pinfunction "1_1") (pintype "passive"))
      (node (ref "C5") (pin "1") (pinfunction "1_1") (pintype "passive"))
      (node (ref "C6") (pin "1") (pinfunction "1_1") (pintype "passive"))
      (node (ref "C7") (pin "1") (pinfunction "1_1") (pintype "passive"))
      (node (ref "C8") (pin "2") (pinfunction "2_2") (pintype "passive"))
      (node (ref "C9") (pin "1") (pinfunction "1_1") (pintype "passive"))
      (node (ref "D10") (pin "A") (pinfunction "A_A") (pintype "passive"))
      (node (ref "D12") (pin "2") (pinfunction "GND_2") (pintype "passive"))
      (node (ref "D13") (pin "2") (pinfunction "A_2") (pintype "passive"))
      (node (ref "D14") (pin "A") (pinfunction "A_A") (pintype "passive"))
      (node (ref "D15") (pin "2") (pinfunction "A_2") (pintype "passive"))
      (node (ref "D4") (pin "A") (pinfunction "A_A") (pintype "passive"))
      (node (ref "D5") (pin "A") (pinfunction "A_A") (pintype "passive"))
      (node (ref "D6") (pin "A") (pinfunction "A_A") (pintype "passive"))
      (node (ref "D8") (pin "A") (pinfunction "A_A") (pintype "passive"))
      (node (ref "D9") (pin "C") (pinfunction "C_C") (pintype "passive"))
      (node (ref "FL1") (pin "2") (pinfunction "2_2") (pintype "passive"))
      (node (ref "J1") (pin "A1") (pinfunction "GND_A1") (pintype "power_in"))
      (node (ref "J1") (pin "A12") (pinfunction "GND_A12") (pintype "power_in"))
      (node (ref "J1") (pin "B1") (pinfunction "GND_B1") (pintype "power_in"))
      (node (ref "J1") (pin "B12") (pinfunction "GND_B12") (pintype "power_in"))
      (node (ref "J2") (pin "2") (pinfunction "GND_2") (pintype "passive"))
      (node (ref "P1") (pin "1") (pinfunction "1_1") (pintype "passive"))
      (node (ref "P1") (pin "2") (pinfunction "2_2") (pintype "passive"))
      (node (ref "Q3") (pin "2") (pinfunction "2_2") (pintype "passive"))
      (node (ref "R14") (pin "1") (pinfunction "1_1") (pintype "passive"))
      (node (ref "R15") (pin "1") (pinfunction "1_1") (pintype "passive"))
      (node (ref "R16") (pin "2") (pinfunction "2_2") (pintype "passive"))
      (node (ref "R17") (pin "1") (pinfunction "1_1") (pintype "passive"))
      (node (ref "R18") (pin "1") (pinfunction "1_1") (pintype "passive"))
      (node (ref "R21") (pin "1") (pinfunction "1_1") (pintype "passive"))
      (node (ref "R30") (pin "1") (pinfunction "1_1") (pintype "passive"))
      (node (ref "R31") (pin "1") (pinfunction "1_1") (pintype "passive"))
      (node (ref "R5") (pin "1") (pinfunction "1_1") (pintype "passive"))
      (node (ref "R7") (pin "2") (pinfunction "2_2") (pintype "passive"))
      (node (ref "R9") (pin "1") (pinfunction "1_1") (pintype "passive"))
      (node (ref "S3") (pin "1") (pinfunction "3_1") (pintype "passive"))
      (node (ref "S3") (pin "3") (pinfunction "1_3") (pintype "passive"))
      (node (ref "TP12") (pin "1") (pinfunction "TPoint_1") (pintype "passive"))
      (node (ref "U1") (pin "15") (pinfunction "GND_15_15") (pintype "power_in"))
      (node (ref "U1") (pin "18") (pinfunction "GND_18_18") (pintype "power_in"))
      (node (ref "U1") (pin "21") (pinfunction "GND_21_21") (pintype "power_in"))
      (node (ref "U1") (pin "26") (pinfunction "GND_26_26") (pintype "power_in"))
      (node (ref "U1") (pin "27") (pinfunction "GND_27_27") (pintype "power_in"))
      (node (ref "U1") (pin "29") (pinfunction "GND_29_29") (pintype "power_in"))
      (node (ref "U1") (pin "34") (pinfunction "GND_34_34") (pintype "power_in"))
      (node (ref "U1") (pin "35") (pinfunction "GND_35_35") (pintype "power_in"))
      (node (ref "U1") (pin "37") (pinfunction "GND_37_37") (pintype "power_in"))
      (node (ref "U1") (pin "4") (pinfunction "GND_4_4") (pintype "power_in"))
      (node (ref "U1") (pin "40") (pinfunction "GND_40_40") (pintype "power_in"))
      (node (ref "U1") (pin "43") (pinfunction "GND_43_43") (pintype "power_in"))
      (node (ref "U1") (pin "50") (pinfunction "GND_50_50") (pintype "power_in"))
      (node (ref "U1") (pin "53") (pinfunction "SHIELD_53") (pintype "passive"))
      (node (ref "U1") (pin "54") (pinfunction "SHIELD_54") (pintype "passive"))
      (node (ref "U1") (pin "9") (pinfunction "GND_9_9") (pintype "power_in"))
      (node (ref "U1") (pin "S1_1") (pinfunction "SHIELD_S1_1") (pintype "passive"))
      (node (ref "U1") (pin "S1_2") (pinfunction "SHIELD_S1_2") (pintype "passive"))
      (node (ref "U1") (pin "S1_3") (pinfunction "SHIELD_S1_3") (pintype "passive"))
      (node (ref "U1") (pin "S2_1") (pinfunction "SHIELD_S2_1") (pintype "passive"))
      (node (ref "U1") (pin "S2_2") (pinfunction "SHIELD_S2_2") (pintype "passive"))
      (node (ref "U1") (pin "S2_3") (pinfunction "SHIELD_S2_3") (pintype "passive"))
      (node (ref "U2") (pin "9") (pinfunction "EP_9") (pintype "passive"))
      (node (ref "U3") (pin "2") (pinfunction "VSS_2") (pintype "passive"))
      (node (ref "U4") (pin "1") (pinfunction "GND_1") (pintype "power_in"))
      (node (ref "U4") (pin "11") (pinfunction "GND_11") (pintype "power_in"))
      (node (ref "U4") (pin "14") (pinfunction "GND_14") (pintype "power_in"))
      (node (ref "U4") (pin "2") (pinfunction "GND_2") (pintype "power_in"))
      (node (ref "U4") (pin "36") (pinfunction "GND_36") (pintype "power_in"))
      (node (ref "U4") (pin "37") (pinfunction "GND_37") (pintype "power_in"))
      (node (ref "U4") (pin "38") (pinfunction "GND_38") (pintype "power_in"))
      (node (ref "U4") (pin "39") (pinfunction "GND_39") (pintype "power_in"))
      (node (ref "U4") (pin "40") (pinfunction "GND_40") (pintype "power_in"))
      (node (ref "U4") (pin "41") (pinfunction "GND_41") (pintype "power_in"))
      (node (ref "U4") (pin "42") (pinfunction "GND_42") (pintype "power_in"))
      (node (ref "U4") (pin "43") (pinfunction "GND_43") (pintype "power_in"))
      (node (ref "U4") (pin "44") (pinfunction "GND_44") (pintype "power_in"))
      (node (ref "U4") (pin "45") (pinfunction "GND_45") (pintype "power_in"))
      (node (ref "U4") (pin "46") (pinfunction "GND_46") (pintype "power_in"))
      (node (ref "U4") (pin "47") (pinfunction "GND_47") (pintype "power_in"))
      (node (ref "U4") (pin "48") (pinfunction "GND_48") (pintype "power_in"))
      (node (ref "U4") (pin "49_1") (pinfunction "GND_49_1") (pintype "power_in"))
      (node (ref "U4") (pin "49_2") (pinfunction "GND_49_2") (pintype "power_in"))
      (node (ref "U4") (pin "49_3") (pinfunction "GND_49_3") (pintype "power_in"))
      (node (ref "U4") (pin "49_4") (pinfunction "GND_49_4") (pintype "power_in"))
      (node (ref "U4") (pin "49_5") (pinfunction "GND_49_5") (pintype "power_in"))
      (node (ref "U4") (pin "49_6") (pinfunction "GND_49_6") (pintype "power_in"))
      (node (ref "U4") (pin "49_7") (pinfunction "GND_49_7") (pintype "power_in"))
      (node (ref "U4") (pin "49_8") (pinfunction "GND_49_8") (pintype "power_in"))
      (node (ref "U4") (pin "49_9") (pinfunction "GND_49_9") (pintype "power_in"))
      (node (ref "U4") (pin "50") (pinfunction "GND_50") (pintype "power_in"))
      (node (ref "U4") (pin "51") (pinfunction "GND_51") (pintype "power_in"))
      (node (ref "U4") (pin "52") (pinfunction "GND_52") (pintype "power_in"))
      (node (ref "U4") (pin "53") (pinfunction "GND_53") (pintype "power_in"))
      (node (ref "U5") (pin "3") (pinfunction "GND_3") (pintype "power_in"))
    )
    (net (code "23") (name "Net-(C11-Pad2)") (class "Default")
      (node (ref "C11") (pin "2") (pinfunction "2_2") (pintype "passive"))
      (node (ref "R8") (pin "1") (pinfunction "1_1") (pintype "passive"))
    )
    (net (code "24") (name "Net-(C19-Pad1)") (class "Default")
      (node (ref "C19") (pin "1") (pintype "passive"))
      (node (ref "J1") (pin "SH1") (pinfunction "SHIELD_SH1") (pintype "power_in"))
      (node (ref "J1") (pin "SH2") (pinfunction "SHIELD_SH2") (pintype "power_in"))
      (node (ref "J1") (pin "SH3") (pinfunction "SHIELD_SH3") (pintype "power_in"))
      (node (ref "J1") (pin "SH4") (pinfunction "SHIELD_SH4") (pintype "power_in"))
      (node (ref "R31") (pin "2") (pinfunction "2_2") (pintype "passive"))
    )
    (net (code "25") (name "Net-(C27-Pad1)") (class "Default")
      (node (ref "C27") (pin "1") (pinfunction "1_1") (pintype "passive"))
      (node (ref "R25") (pin "1") (pinfunction "1_1") (pintype "passive"))
      (node (ref "R26") (pin "1") (pinfunction "1_1") (pintype "passive"))
      (node (ref "Y1") (pin "1") (pinfunction "1_1") (pintype "passive"))
    )
    (net (code "26") (name "Net-(D2-A)") (class "Default")
      (node (ref "D2") (pin "1") (pinfunction "A_1") (pintype "passive"))
      (node (ref "Q1") (pin "3") (pinfunction "3_3") (pintype "passive"))
    )
    (net (code "27") (name "Net-(D3-PadA)") (class "Default")
      (node (ref "D3") (pin "A") (pinfunction "A_A") (pintype "passive"))
      (node (ref "R19") (pin "2") (pinfunction "2_2") (pintype "passive"))
    )
    (net (code "28") (name "Net-(D7-PadC)") (class "Default")
      (node (ref "D7") (pin "C") (pinfunction "C_C") (pintype "passive"))
      (node (ref "R22") (pin "2") (pinfunction "2_2") (pintype "passive"))
    )
    (net (code "29") (name "Net-(D9-PadA)") (class "Default")
      (node (ref "D9") (pin "A") (pinfunction "A_A") (pintype "passive"))
      (node (ref "R20") (pin "2") (pinfunction "2_2") (pintype "passive"))
    )
    (net (code "30") (name "Net-(D11-PadA)") (class "Default")
      (node (ref "D11") (pin "A") (pinfunction "A_A") (pintype "passive"))
      (node (ref "R24") (pin "2") (pinfunction "2_2") (pintype "passive"))
    )
    (net (code "31") (name "Net-(J1-CC1)") (class "Default")
      (node (ref "J1") (pin "A5") (pinfunction "CC1_A5") (pintype "bidirectional"))
      (node (ref "R18") (pin "2") (pinfunction "2_2") (pintype "passive"))
    )
    (net (code "32") (name "Net-(J1-CC2)") (class "Default")
      (node (ref "J1") (pin "B5") (pinfunction "CC2_B5") (pintype "bidirectional"))
      (node (ref "R30") (pin "2") (pinfunction "2_2") (pintype "passive"))
    )
    (net (code "33") (name "Net-(Q1-Pad1)") (class "Default")
      (node (ref "Q1") (pin "1") (pinfunction "1_1") (pintype "passive"))
      (node (ref "R1") (pin "2") (pinfunction "2_2") (pintype "passive"))
    )
    (net (code "34") (name "Net-(Q2-Pad1)") (class "Default")
      (node (ref "Q2") (pin "1") (pinfunction "1_1") (pintype "passive"))
      (node (ref "R11") (pin "1") (pinfunction "1_1") (pintype "passive"))
    )
    (net (code "35") (name "Net-(Q2-Pad3)") (class "Default")
      (node (ref "Q2") (pin "3") (pinfunction "3_3") (pintype "passive"))
      (node (ref "R12") (pin "2") (pinfunction "2_2") (pintype "passive"))
    )
    (net (code "36") (name "Net-(Q3-Pad1)") (class "Default")
      (node (ref "Q3") (pin "1") (pinfunction "1_1") (pintype "passive"))
      (node (ref "R13") (pin "2") (pinfunction "2_2") (pintype "passive"))
      (node (ref "R17") (pin "2") (pinfunction "2_2") (pintype "passive"))
    )
    (net (code "37") (name "Net-(Q3-Pad3)") (class "Default")
      (node (ref "Q3") (pin "3") (pinfunction "3_3") (pintype "passive"))
      (node (ref "R10") (pin "1") (pinfunction "1_1") (pintype "passive"))
      (node (ref "R11") (pin "2") (pinfunction "2_2") (pintype "passive"))
    )
    (net (code "38") (name "Net-(U1-UART_RX)") (class "Default")
      (node (ref "R2") (pin "2") (pinfunction "2_2") (pintype "passive"))
      (node (ref "U1") (pin "11") (pinfunction "UART_RX_11") (pintype "bidirectional"))
    )
    (net (code "39") (name "Net-(U1-UART_TX)") (class "Default")
      (node (ref "R6") (pin "2") (pinfunction "2_2") (pintype "passive"))
      (node (ref "U1") (pin "13") (pinfunction "UART_TX_13") (pintype "bidirectional"))
    )
    (net (code "40") (name "Net-(U2-COMP)") (class "Default")
      (node (ref "R8") (pin "2") (pinfunction "2_2") (pintype "passive"))
      (node (ref "U2") (pin "1") (pinfunction "COMP_1") (pintype "passive"))
    )
    (net (code "41") (name "Net-(U2-FB)") (class "Default")
      (node (ref "R4") (pin "2") (pinfunction "2_2") (pintype "passive"))
      (node (ref "R7") (pin "1") (pinfunction "1_1") (pintype "passive"))
      (node (ref "U2") (pin "7") (pinfunction "FB_7") (pintype "passive"))
    )
    (net (code "42") (name "Net-(U2-PGOOD)") (class "Default")
      (node (ref "R29") (pin "1") (pinfunction "1_1") (pintype "passive"))
      (node (ref "U2") (pin "8") (pinfunction "PGOOD_8") (pintype "passive"))
    )
    (net (code "43") (name "Net-(U2-RT)") (class "Default")
      (node (ref "R9") (pin "2") (pinfunction "2_2") (pintype "passive"))
      (node (ref "U2") (pin "6") (pinfunction "RT_6") (pintype "passive"))
    )
    (net (code "44") (name "Net-(U2-SS)") (class "Default")
      (node (ref "C10") (pin "2") (pinfunction "2_2") (pintype "passive"))
      (node (ref "U2") (pin "2") (pinfunction "SS_2") (pintype "passive"))
    )
    (net (code "45") (name "Net-(U3-PROG)") (class "Default")
      (node (ref "R21") (pin "2") (pinfunction "2_2") (pintype "passive"))
      (node (ref "U3") (pin "5") (pinfunction "PROG_5") (pintype "passive"))
    )
    (net (code "46") (name "Net-(U4-IO0)") (class "Default")
      (node (ref "C26") (pin "1") (pinfunction "1_1") (pintype "passive"))
      (node (ref "R25") (pin "2") (pinfunction "2_2") (pintype "passive"))
      (node (ref "U4") (pin "12") (pinfunction "IO0_12") (pintype "bidirectional"))
      (node (ref "Y1") (pin "2") (pinfunction "2_2") (pintype "passive"))
    )
    (net (code "47") (name "Net-(U4-IO1)") (class "Default")
      (node (ref "R26") (pin "2") (pinfunction "2_2") (pintype "passive"))
      (node (ref "U4") (pin "13") (pinfunction "IO1_13") (pintype "bidirectional"))
    )
    (net (code "48") (name "Net-(U4-IO3)") (class "Default")
      (node (ref "R28") (pin "1") (pinfunction "1_1") (pintype "passive"))
      (node (ref "U4") (pin "6") (pinfunction "IO3_6") (pintype "bidirectional"))
    )
    (net (code "49") (name "Net-(U4-IO8)") (class "Default")
      (node (ref "R33") (pin "1") (pinfunction "1_1") (pintype "passive"))
      (node (ref "U4") (pin "22") (pinfunction "IO8_22") (pintype "bidirectional"))
    )
    (net (code "50") (name "Net-(U5-A)") (class "Default")
      (node (ref "R27") (pin "2") (pinfunction "2_2") (pintype "passive"))
      (node (ref "U5") (pin "2") (pinfunction "A_2") (pintype "passive"))
    )
    (net (code "51") (name "VBAT") (class "Default")
      (node (ref "Q1") (pin "2") (pinfunction "2_2") (pintype "passive"))
      (node (ref "Q2") (pin "2") (pinfunction "2_2") (pintype "passive"))
      (node (ref "R10") (pin "2") (pinfunction "2_2") (pintype "passive"))
      (node (ref "S1") (pin "2") (pinfunction "2_2") (pintype "passive"))
      (node (ref "S1") (pin "4") (pinfunction "4_4") (pintype "passive"))
      (node (ref "TP1") (pin "1") (pinfunction "TPoint_1") (pintype "passive"))
    )
    (net (code "52") (name "VBAT_IN") (class "Default")
      (node (ref "C21") (pin "1") (pinfunction "1_1") (pintype "passive"))
      (node (ref "D15") (pin "1") (pinfunction "K_1") (pintype "passive"))
      (node (ref "J2") (pin "1") (pinfunction "VBAT_1") (pintype "passive"))
      (node (ref "S1") (pin "1") (pinfunction "1_1") (pintype "passive"))
      (node (ref "S1") (pin "3") (pinfunction "3_3") (pintype "passive"))
      (node (ref "U3") (pin "3") (pinfunction "VBAT_3") (pintype "passive"))
    )
    (net (code "53") (name "VBUS_USB") (class "Default")
      (node (ref "D13") (pin "1") (pinfunction "K_1") (pintype "passive"))
      (node (ref "J1") (pin "A4") (pinfunction "VBUS_A4") (pintype "power_in"))
      (node (ref "J1") (pin "A9") (pinfunction "VBUS_A9") (pintype "power_in"))
      (node (ref "J1") (pin "B4") (pinfunction "VBUS_B4") (pintype "power_in"))
      (node (ref "J1") (pin "B9") (pinfunction "VBUS_B9") (pintype "power_in"))
      (node (ref "L1") (pin "2") (pintype "passive"))
    )
    (net (code "54") (name "V_USB") (class "Default")
      (node (ref "C20") (pin "1") (pinfunction "1_1") (pintype "passive"))
      (node (ref "C28") (pin "2") (pinfunction "2_2") (pintype "passive"))
      (node (ref "C6") (pin "2") (pinfunction "2_2") (pintype "passive"))
      (node (ref "D1") (pin "1") (pinfunction "A_1") (pintype "passive"))
      (node (ref "D7") (pin "A") (pinfunction "A_A") (pintype "passive"))
      (node (ref "L1") (pin "1") (pintype "passive"))
      (node (ref "R1") (pin "1") (pinfunction "1_1") (pintype "passive"))
      (node (ref "R24") (pin "1") (pinfunction "1_1") (pintype "passive"))
      (node (ref "R5") (pin "2") (pinfunction "2_2") (pintype "passive"))
      (node (ref "U3") (pin "4") (pinfunction "VDD_4") (pintype "passive"))
      (node (ref "U5") (pin "5") (pinfunction "VCC_5") (pintype "power_in"))
    )
    (net (code "55") (name "Vmodem") (class "Default")
      (node (ref "C1") (pin "1") (pinfunction "1_1") (pintype "passive"))
      (node (ref "C12") (pin "1") (pinfunction "1_1") (pintype "passive"))
      (node (ref "C13") (pin "2") (pinfunction "2_2") (pintype "passive"))
      (node (ref "C14") (pin "2") (pinfunction "2_2") (pintype "passive"))
      (node (ref "C15") (pin "2") (pinfunction "2_2") (pintype "passive"))
      (node (ref "C2") (pin "2") (pinfunction "2_2") (pintype "passive"))
      (node (ref "C3") (pin "2") (pinfunction "2_2") (pintype "passive"))
      (node (ref "C4") (pin "2") (pinfunction "2_2") (pintype "passive"))
      (node (ref "C5") (pin "2") (pinfunction "2_2") (pintype "passive"))
      (node (ref "FL1") (pin "3") (pinfunction "OUT/IN_3") (pintype "passive"))
      (node (ref "U1") (pin "2") (pinfunction "VDD_2_2") (pintype "power_in"))
      (node (ref "U1") (pin "39") (pinfunction "VDD_39_39") (pintype "power_in"))
      (node (ref "U1") (pin "41") (pinfunction "VDD_41_41") (pintype "power_in"))
      (node (ref "U1") (pin "52") (pinfunction "VDD_52_52") (pintype "power_in"))
    )
    (net (code "56") (name "unconnected-(Fid1-Pad0)") (class "Default")
      (node (ref "Fid1") (pin "0") (pinfunction "0_0") (pintype "passive"))
    )
    (net (code "57") (name "unconnected-(Fid2-Pad0)") (class "Default")
      (node (ref "Fid2") (pin "0") (pinfunction "0_0") (pintype "passive"))
    )
    (net (code "58") (name "unconnected-(Fid3-Pad0)") (class "Default")
      (node (ref "Fid3") (pin "0") (pinfunction "0_0") (pintype "passive"))
    )
    (net (code "59") (name "unconnected-(J1-SBU1-PadA8)") (class "Default")
      (node (ref "J1") (pin "A8") (pinfunction "SBU1_A8") (pintype "bidirectional"))
    )
    (net (code "60") (name "unconnected-(J1-SBU2-PadB8)") (class "Default")
      (node (ref "J1") (pin "B8") (pinfunction "SBU2_B8") (pintype "bidirectional"))
    )
    (net (code "61") (name "unconnected-(J1-SSRXN1-PadB10)") (class "Default")
      (node (ref "J1") (pin "B10") (pinfunction "SSRXN1_B10") (pintype "bidirectional"))
    )
    (net (code "62") (name "unconnected-(J1-SSRXN2-PadA10)") (class "Default")
      (node (ref "J1") (pin "A10") (pinfunction "SSRXN2_A10") (pintype "bidirectional"))
    )
    (net (code "63") (name "unconnected-(J1-SSRXP1-PadB11)") (class "Default")
      (node (ref "J1") (pin "B11") (pinfunction "SSRXP1_B11") (pintype "bidirectional"))
    )
    (net (code "64") (name "unconnected-(J1-SSRXP2-PadA11)") (class "Default")
      (node (ref "J1") (pin "A11") (pinfunction "SSRXP2_A11") (pintype "bidirectional"))
    )
    (net (code "65") (name "unconnected-(J1-SSTXN1-PadA3)") (class "Default")
      (node (ref "J1") (pin "A3") (pinfunction "SSTXN1_A3") (pintype "bidirectional"))
    )
    (net (code "66") (name "unconnected-(J1-SSTXN2-PadB3)") (class "Default")
      (node (ref "J1") (pin "B3") (pinfunction "SSTXN2_B3") (pintype "bidirectional"))
    )
    (net (code "67") (name "unconnected-(J1-SSTXP1-PadA2)") (class "Default")
      (node (ref "J1") (pin "A2") (pinfunction "SSTXP1_A2") (pintype "bidirectional"))
    )
    (net (code "68") (name "unconnected-(J1-SSTXP2-PadB2)") (class "Default")
      (node (ref "J1") (pin "B2") (pinfunction "SSTXP2_B2") (pintype "bidirectional"))
    )
    (net (code "69") (name "unconnected-(U1-NC_1-Pad1)") (class "Default")
      (node (ref "U1") (pin "1") (pinfunction "NC_1_1") (pintype "passive"))
    )
    (net (code "70") (name "unconnected-(U1-NC_3-Pad3)") (class "Default")
      (node (ref "U1") (pin "3") (pinfunction "NC_3_3") (pintype "passive"))
    )
    (net (code "71") (name "unconnected-(U1-NC_5-Pad5)") (class "Default")
      (node (ref "U1") (pin "5") (pinfunction "NC_5_5") (pintype "passive"))
    )
    (net (code "72") (name "unconnected-(U1-NC_6-Pad6)") (class "Default")
      (node (ref "U1") (pin "6") (pinfunction "NC_6_6") (pintype "passive"))
    )
    (net (code "73") (name "unconnected-(U1-NC_7-Pad7)") (class "Default")
      (node (ref "U1") (pin "7") (pinfunction "NC_7_7") (pintype "passive"))
    )
    (net (code "74") (name "unconnected-(U1-NC_8-Pad8)") (class "Default")
      (node (ref "U1") (pin "8") (pinfunction "NC_8_8") (pintype "passive"))
    )
    (net (code "75") (name "unconnected-(U1-NC_10-Pad10)") (class "Default")
      (node (ref "U1") (pin "10") (pinfunction "NC_10_10") (pintype "passive"))
    )
    (net (code "76") (name "unconnected-(U1-NC_12-Pad12)") (class "Default")
      (node (ref "U1") (pin "12") (pinfunction "NC_12_12") (pintype "passive"))
    )
    (net (code "77") (name "unconnected-(U1-NC_14-Pad14)") (class "Default")
      (node (ref "U1") (pin "14") (pinfunction "NC_14_14") (pintype "passive"))
    )
    (net (code "78") (name "unconnected-(U1-NC_16-Pad16)") (class "Default")
      (node (ref "U1") (pin "16") (pinfunction "NC_16_16") (pintype "passive"))
    )
    (net (code "79") (name "unconnected-(U1-NC_19-Pad19)") (class "Default")
      (node (ref "U1") (pin "19") (pinfunction "NC_19_19") (pintype "passive"))
    )
    (net (code "80") (name "unconnected-(U1-NC_20-Pad20)") (class "Default")
      (node (ref "U1") (pin "20") (pinfunction "NC_20_20") (pintype "passive"))
    )
    (net (code "81") (name "unconnected-(U1-NC_22-Pad22)") (class "Default")
      (node (ref "U1") (pin "22") (pinfunction "NC_22_22") (pintype "passive"))
    )
    (net (code "82") (name "unconnected-(U1-NC_23-Pad23)") (class "Default")
      (node (ref "U1") (pin "23") (pinfunction "NC_23_23") (pintype "passive"))
    )
    (net (code "83") (name "unconnected-(U1-NC_24-Pad24)") (class "Default")
      (node (ref "U1") (pin "24") (pinfunction "NC_24_24") (pintype "passive"))
    )
    (net (code "84") (name "unconnected-(U1-NC_25-Pad25)") (class "Default")
      (node (ref "U1") (pin "25") (pinfunction "NC_25_25") (pintype "passive"))
    )
    (net (code "85") (name "unconnected-(U1-NC_28-Pad28)") (class "Default")
      (node (ref "U1") (pin "28") (pinfunction "NC_28_28") (pintype "passive"))
    )
    (net (code "86") (name "unconnected-(U1-NC_30-Pad30)") (class "Default")
      (node (ref "U1") (pin "30") (pinfunction "NC_30_30") (pintype "passive"))
    )
    (net (code "87") (name "unconnected-(U1-NC_31-Pad31)") (class "Default")
      (node (ref "U1") (pin "31") (pinfunction "NC_31_31") (pintype "passive"))
    )
    (net (code "88") (name "unconnected-(U1-NC_32-Pad32)") (class "Default")
      (node (ref "U1") (pin "32") (pinfunction "NC_32_32") (pintype "passive"))
    )
    (net (code "89") (name "unconnected-(U1-NC_33-Pad33)") (class "Default")
      (node (ref "U1") (pin "33") (pinfunction "NC_33_33") (pintype "passive"))
    )
    (net (code "90") (name "unconnected-(U1-NC_36-Pad36)") (class "Default")
      (node (ref "U1") (pin "36") (pinfunction "NC_36_36") (pintype "passive"))
    )
    (net (code "91") (name "unconnected-(U1-NC_38-Pad38)") (class "Default")
      (node (ref "U1") (pin "38") (pinfunction "NC_38_38") (pintype "passive"))
    )
    (net (code "92") (name "unconnected-(U1-NC_44-Pad44)") (class "Default")
      (node (ref "U1") (pin "44") (pinfunction "NC_44_44") (pintype "passive"))
    )
    (net (code "93") (name "unconnected-(U1-NC_45-Pad45)") (class "Default")
      (node (ref "U1") (pin "45") (pinfunction "NC_45_45") (pintype "passive"))
    )
    (net (code "94") (name "unconnected-(U1-NC_46-Pad46)") (class "Default")
      (node (ref "U1") (pin "46") (pinfunction "NC_46_46") (pintype "passive"))
    )
    (net (code "95") (name "unconnected-(U1-NC_47-Pad47)") (class "Default")
      (node (ref "U1") (pin "47") (pinfunction "NC_47_47") (pintype "passive"))
    )
    (net (code "96") (name "unconnected-(U1-NC_48-Pad48)") (class "Default")
      (node (ref "U1") (pin "48") (pinfunction "NC_48_48") (pintype "passive"))
    )
    (net (code "97") (name "unconnected-(U1-NC_49-Pad49)") (class "Default")
      (node (ref "U1") (pin "49") (pinfunction "NC_49_49") (pintype "passive"))
    )
    (net (code "98") (name "unconnected-(U1-NC_51-Pad51)") (class "Default")
      (node (ref "U1") (pin "51") (pinfunction "NC_51_51") (pintype "passive"))
    )
    (net (code "99") (name "unconnected-(U1-T{slash}R_OUTPUT-Pad17)") (class "Default")
      (node (ref "U1") (pin "17") (pinfunction "T/R_OUTPUT_17") (pintype "passive"))
    )
    (net (code "100") (name "unconnected-(U4-NC-Pad4)") (class "Default")
      (node (ref "U4") (pin "4") (pinfunction "NC_4") (pintype "passive"))
    )
    (net (code "101") (name "unconnected-(U4-NC-Pad7)") (class "Default")
      (node (ref "U4") (pin "7") (pinfunction "NC_7") (pintype "passive"))
    )
    (net (code "102") (name "unconnected-(U4-NC-Pad9)") (class "Default")
      (node (ref "U4") (pin "9") (pinfunction "NC_9") (pintype "passive"))
    )
    (net (code "103") (name "unconnected-(U4-NC-Pad10)") (class "Default")
      (node (ref "U4") (pin "10") (pinfunction "NC_10") (pintype "passive"))
    )
    (net (code "104") (name "unconnected-(U4-NC-Pad15)") (class "Default")
      (node (ref "U4") (pin "15") (pinfunction "NC_15") (pintype "passive"))
    )
    (net (code "105") (name "unconnected-(U4-NC-Pad17)") (class "Default")
      (node (ref "U4") (pin "17") (pinfunction "NC_17") (pintype "passive"))
    )
    (net (code "106") (name "unconnected-(U4-NC-Pad24)") (class "Default")
      (node (ref "U4") (pin "24") (pinfunction "NC_24") (pintype "passive"))
    )
    (net (code "107") (name "unconnected-(U4-NC-Pad25)") (class "Default")
      (node (ref "U4") (pin "25") (pinfunction "NC_25") (pintype "passive"))
    )
    (net (code "108") (name "unconnected-(U4-NC-Pad28)") (class "Default")
      (node (ref "U4") (pin "28") (pinfunction "NC_28") (pintype "passive"))
    )
    (net (code "109") (name "unconnected-(U4-NC-Pad29)") (class "Default")
      (node (ref "U4") (pin "29") (pinfunction "NC_29") (pintype "passive"))
    )
    (net (code "110") (name "unconnected-(U4-NC-Pad32)") (class "Default")
      (node (ref "U4") (pin "32") (pinfunction "NC_32") (pintype "passive"))
    )
    (net (code "111") (name "unconnected-(U4-NC-Pad33)") (class "Default")
      (node (ref "U4") (pin "33") (pinfunction "NC_33") (pintype "passive"))
    )
    (net (code "112") (name "unconnected-(U4-NC-Pad34)") (class "Default")
      (node (ref "U4") (pin "34") (pinfunction "NC_34") (pintype "passive"))
    )
    (net (code "113") (name "unconnected-(U4-NC-Pad35)") (class "Default")
      (node (ref "U4") (pin "35") (pinfunction "NC_35") (pintype "passive"))
    )
    (net (code "114") (name "unconnected-(U5-NC-Pad1)") (class "Default")
      (node (ref "U5") (pin "1") (pinfunction "NC_1") (pintype "passive"))
    )
  )
)
